# display_e7.net
KiCad netlist of a schematic drawn in EAGLE
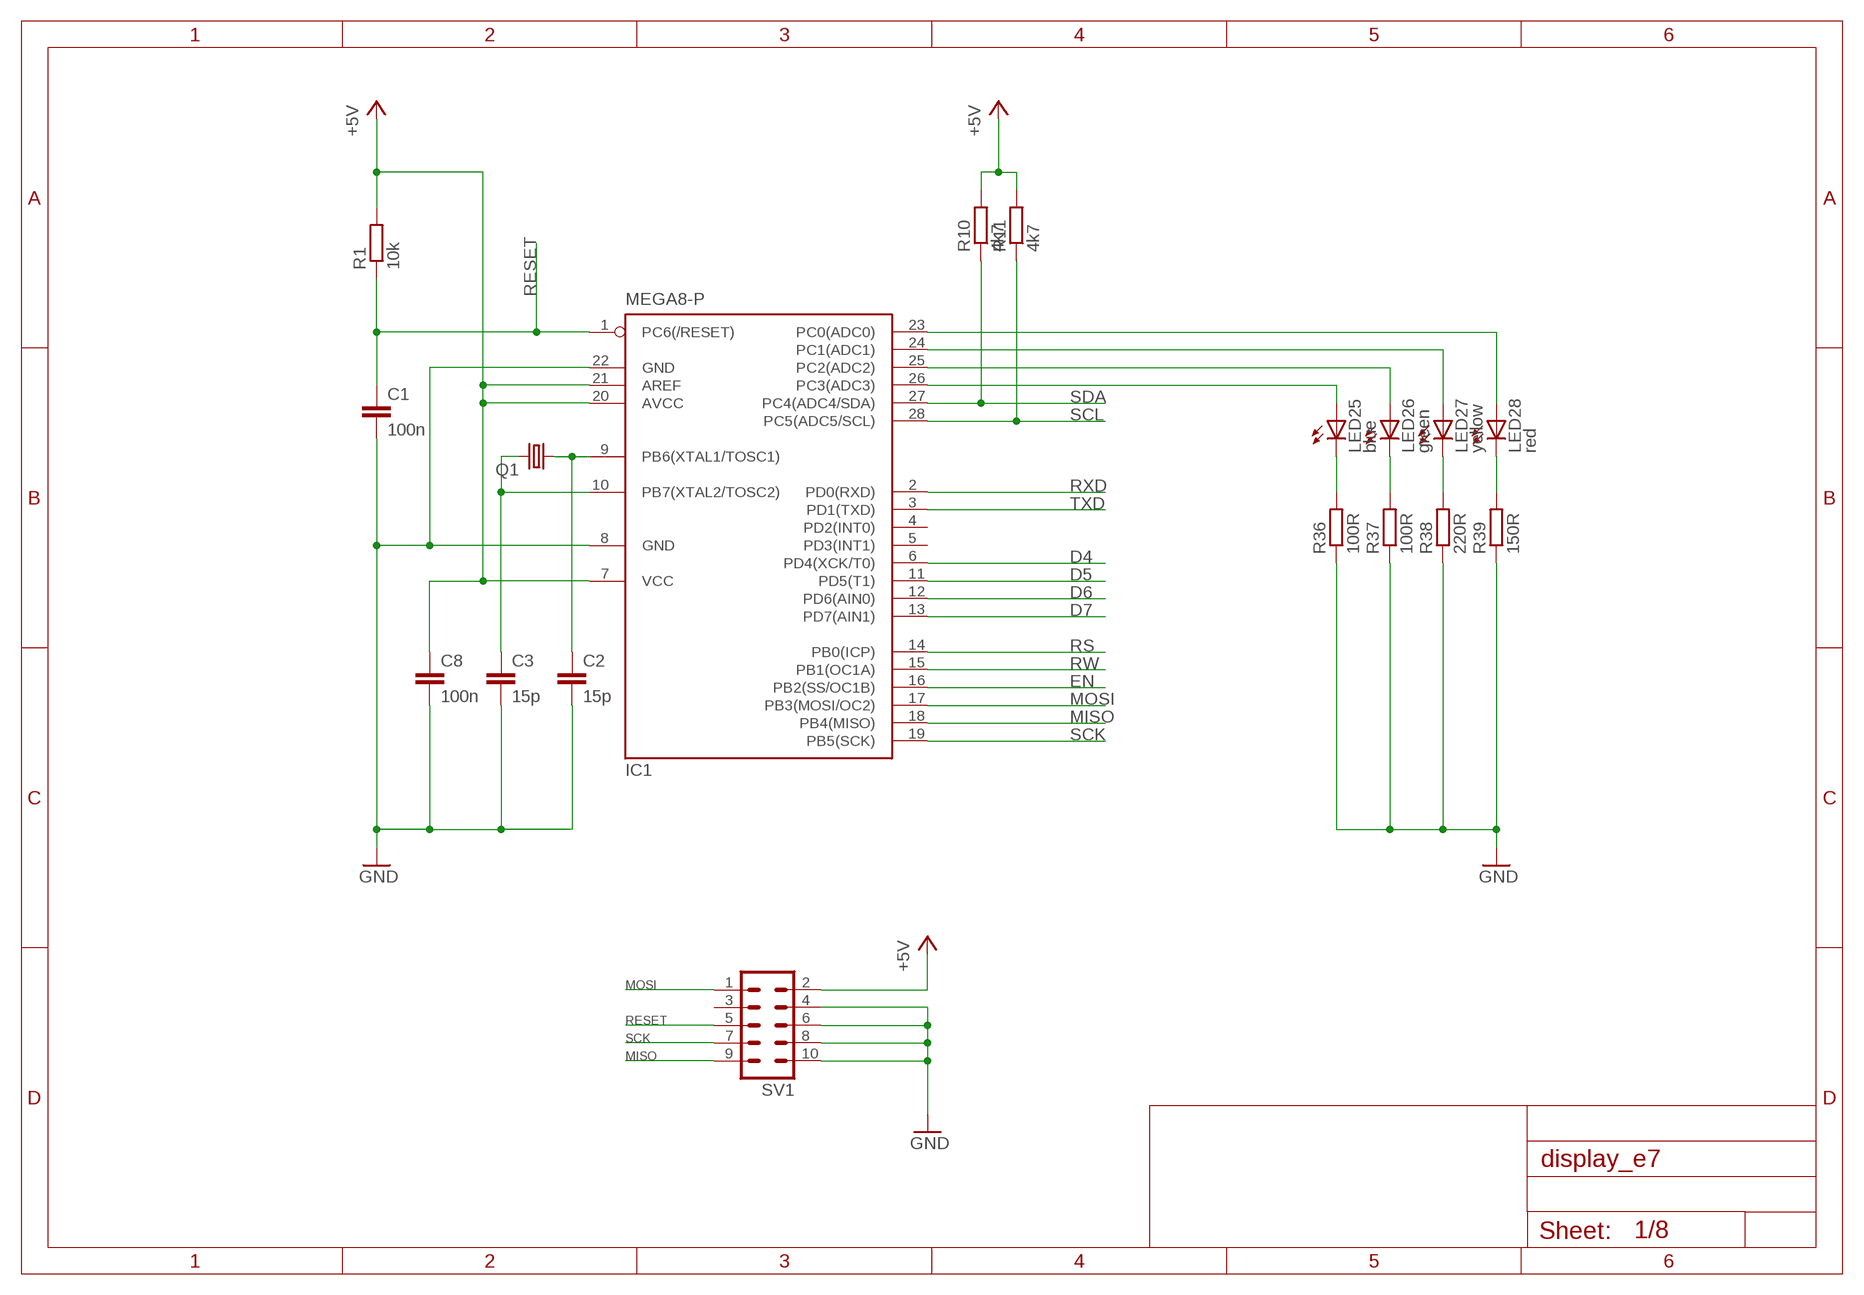
[diagram p0: schematic, sheet 1]
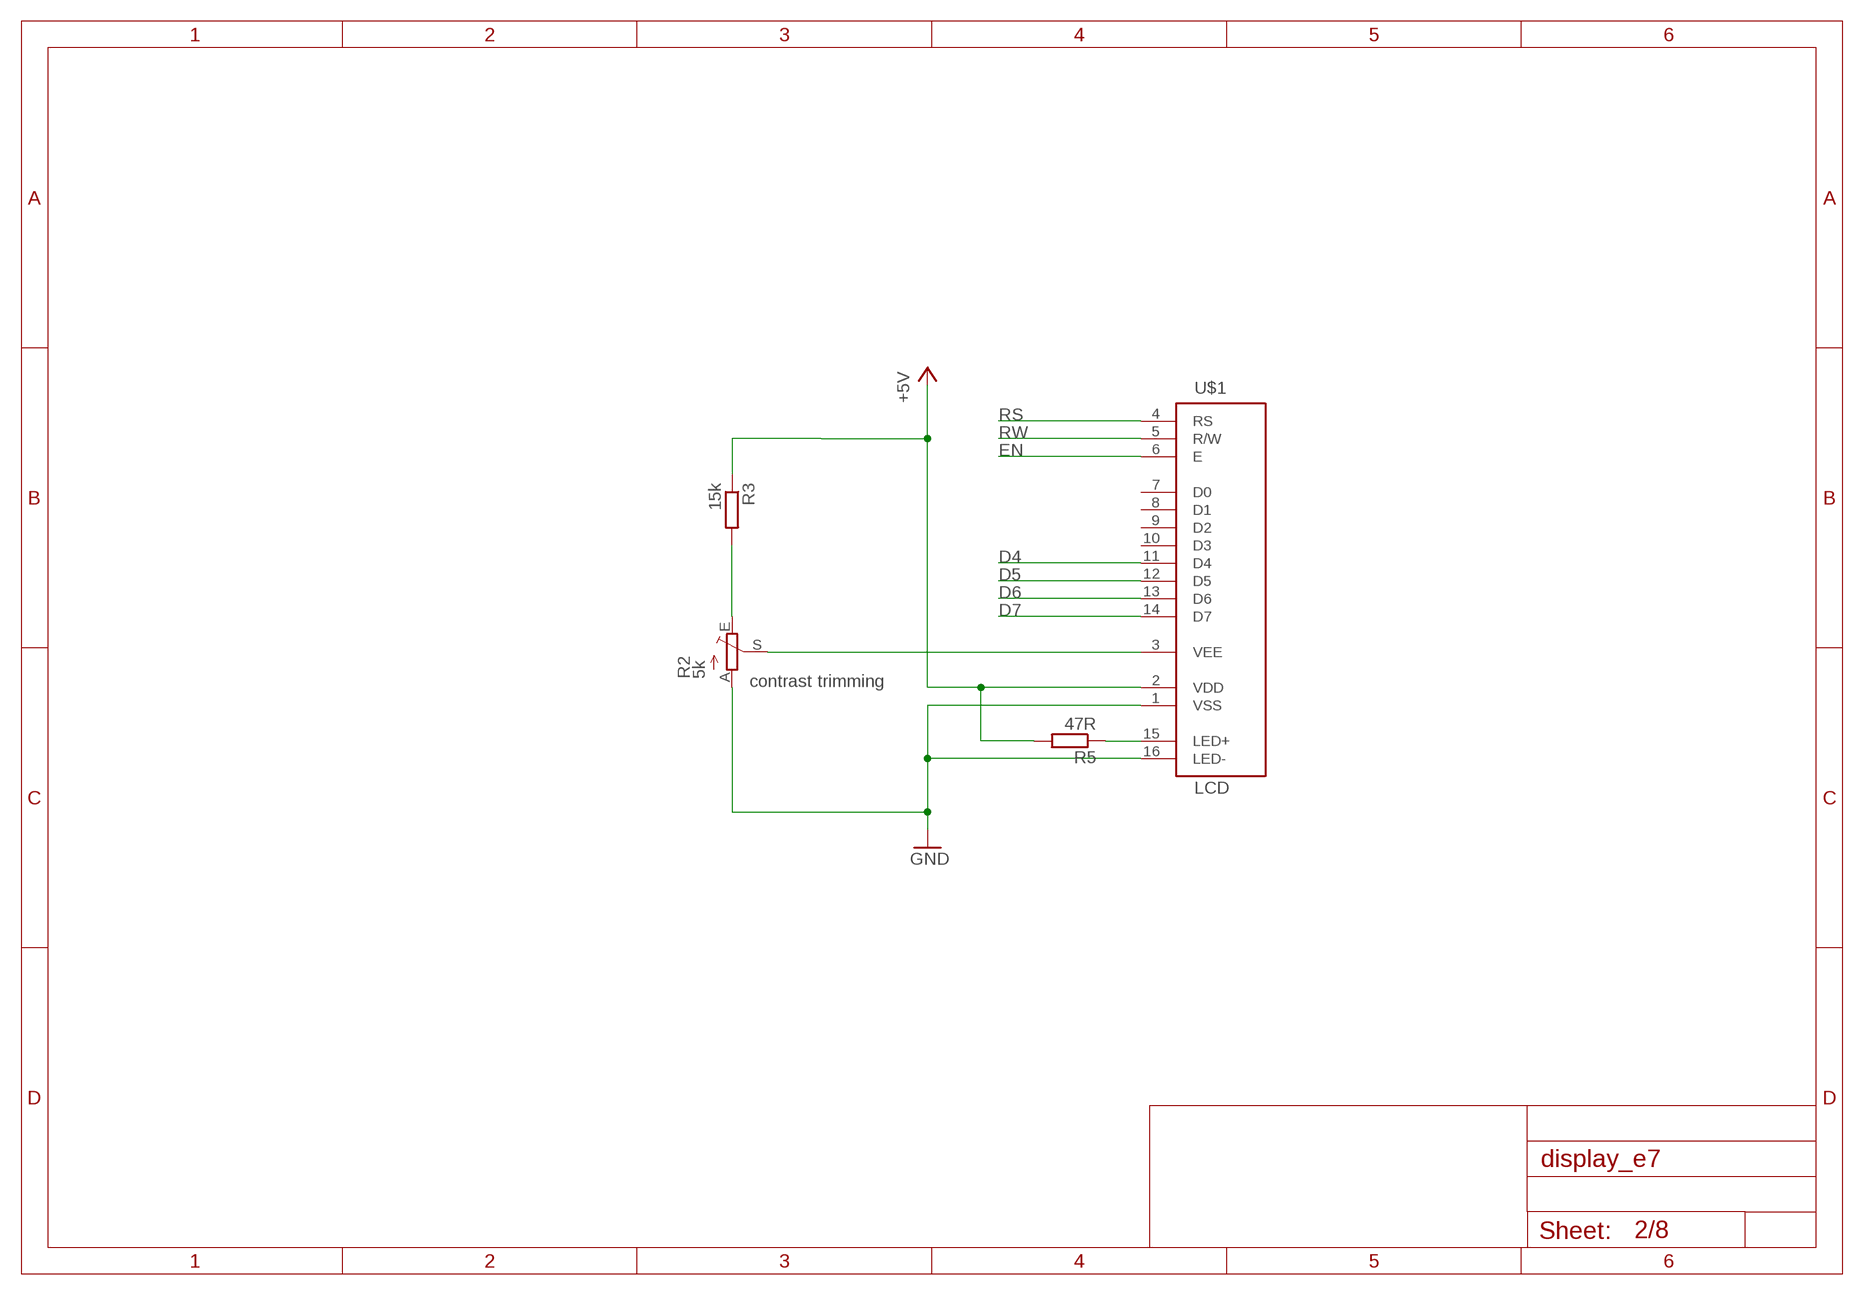
[diagram p1: schematic, sheet 2]
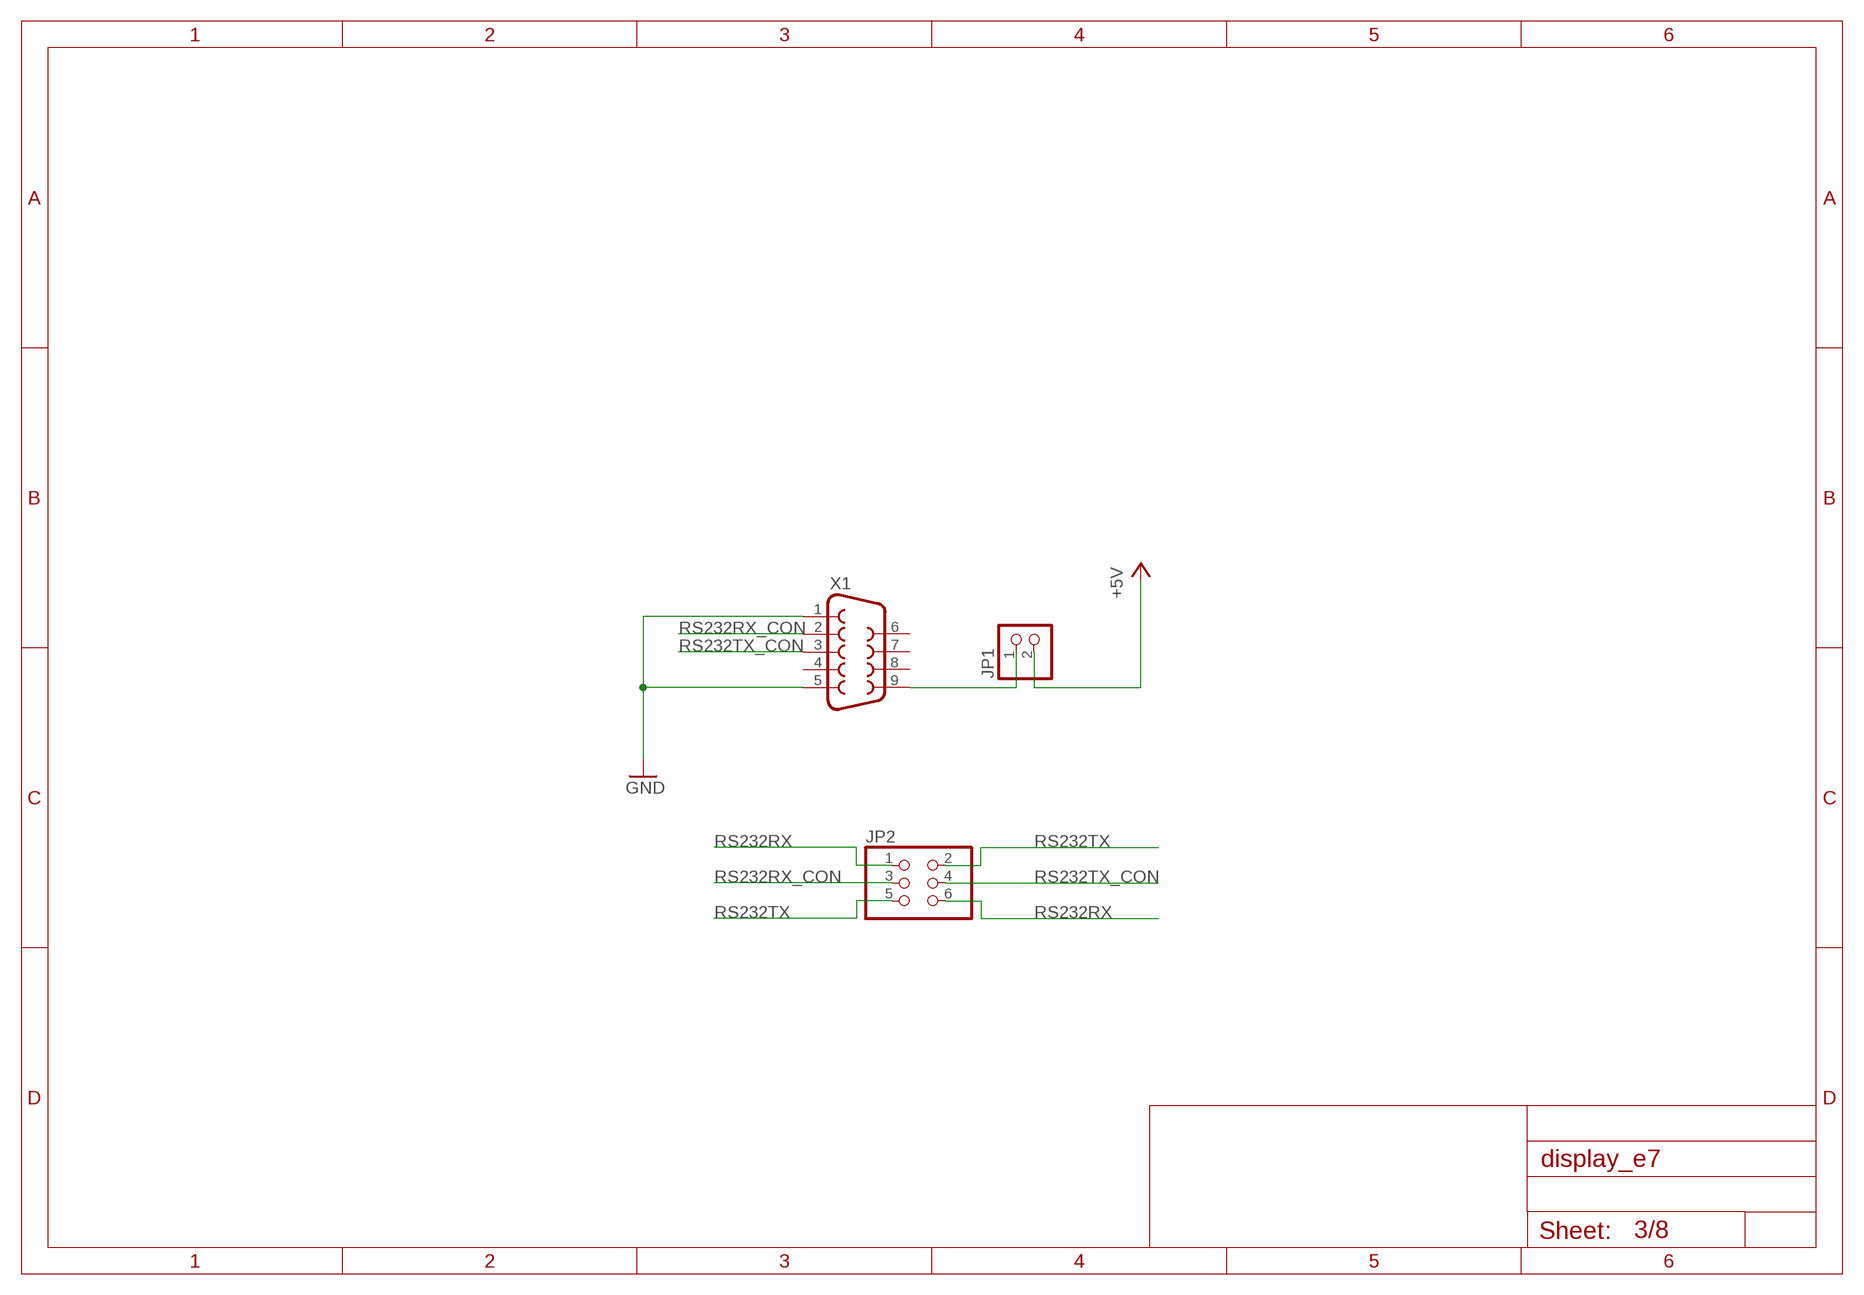
[diagram p2: schematic, sheet 3]
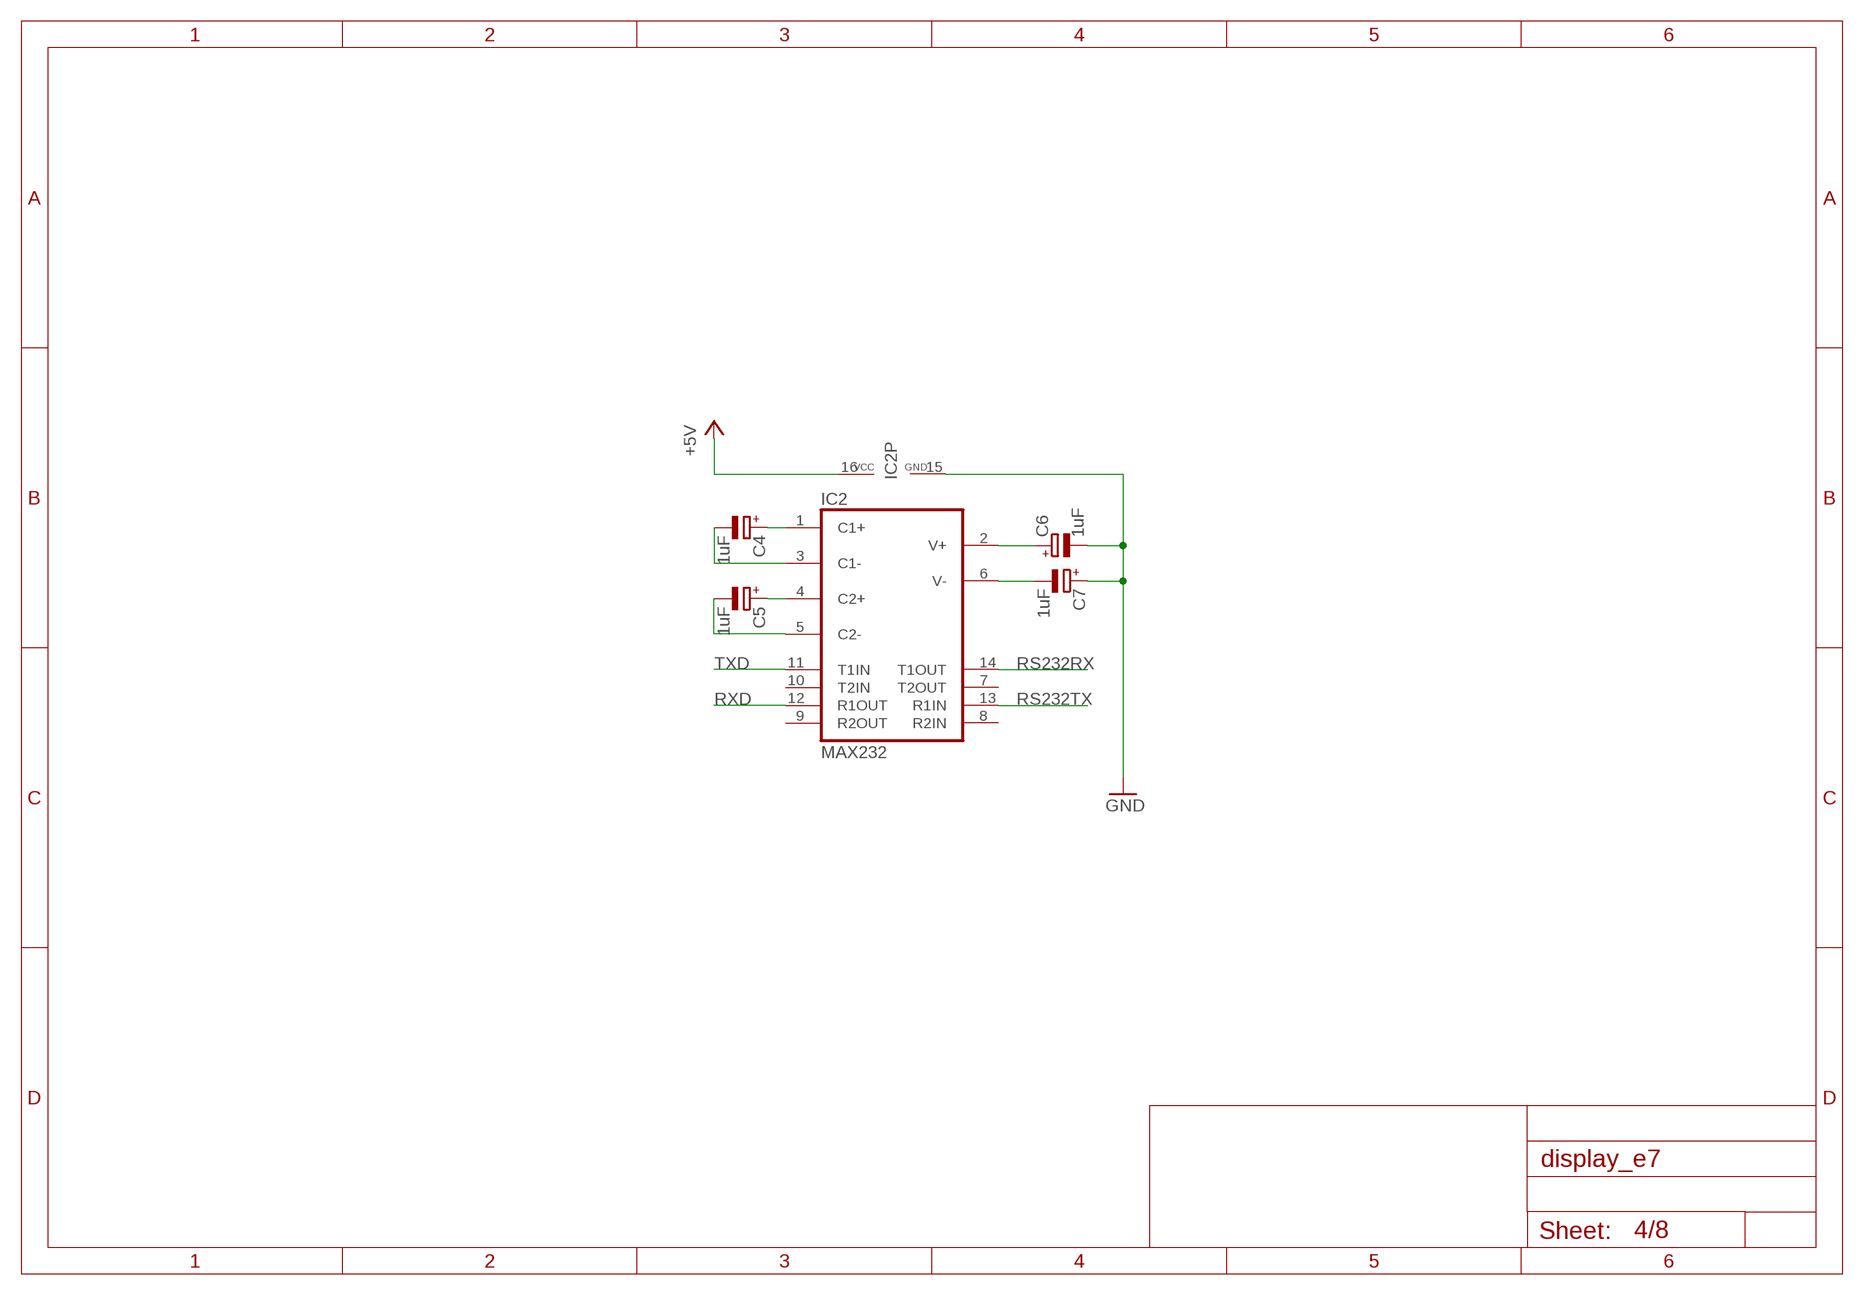
[diagram p3: schematic, sheet 4]
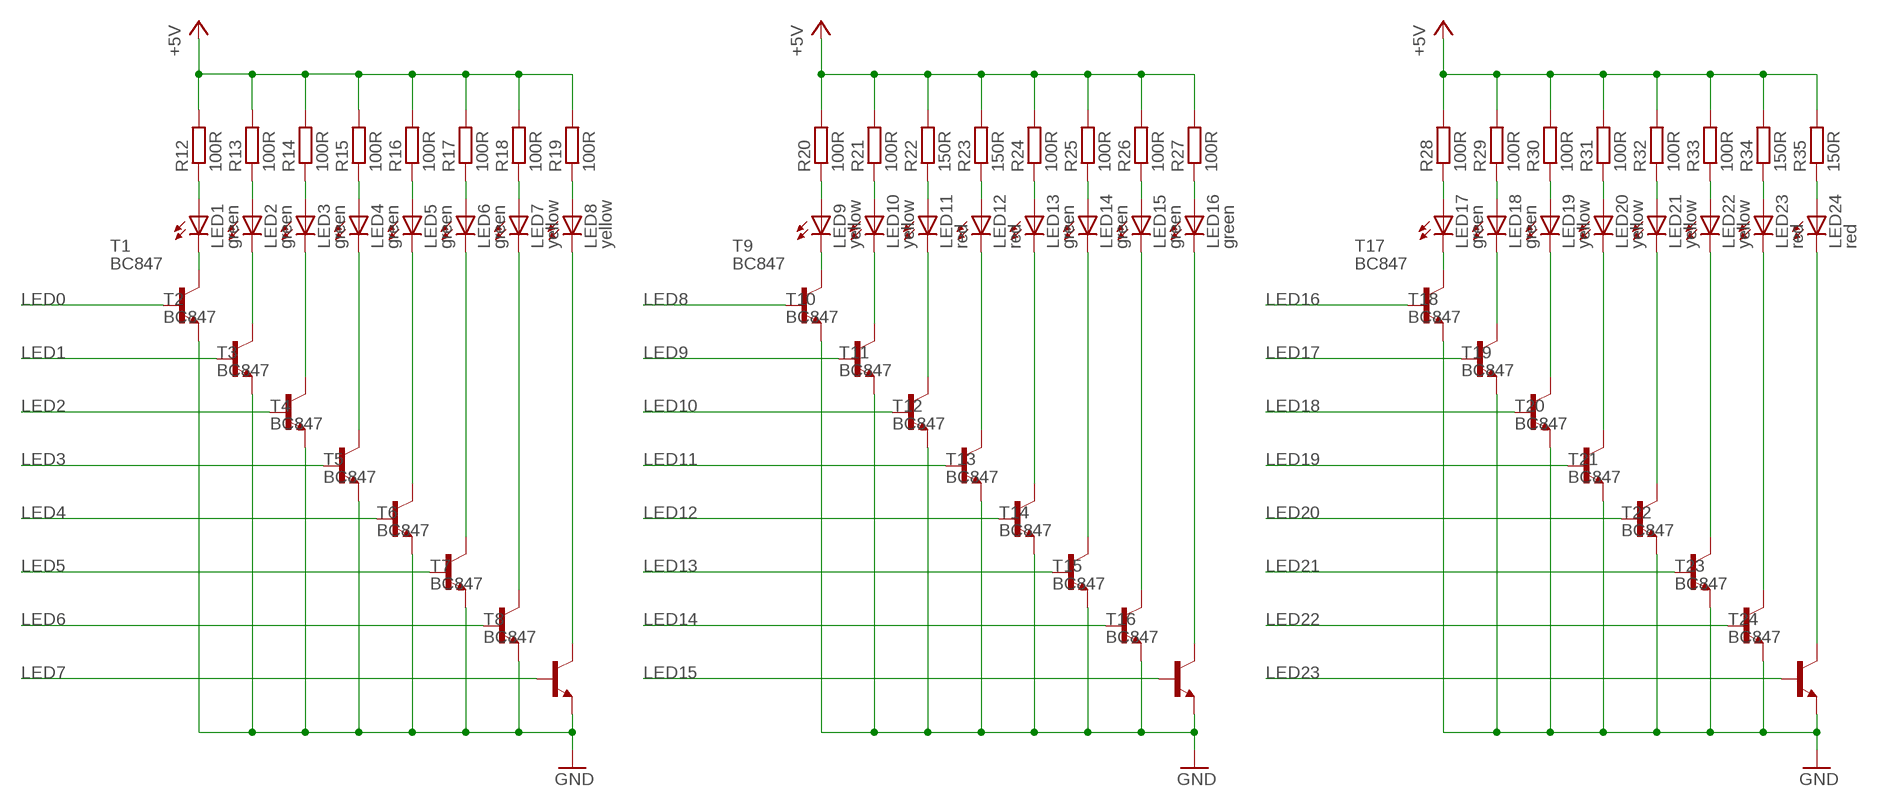
[diagram p4: schematic, sheet 5]
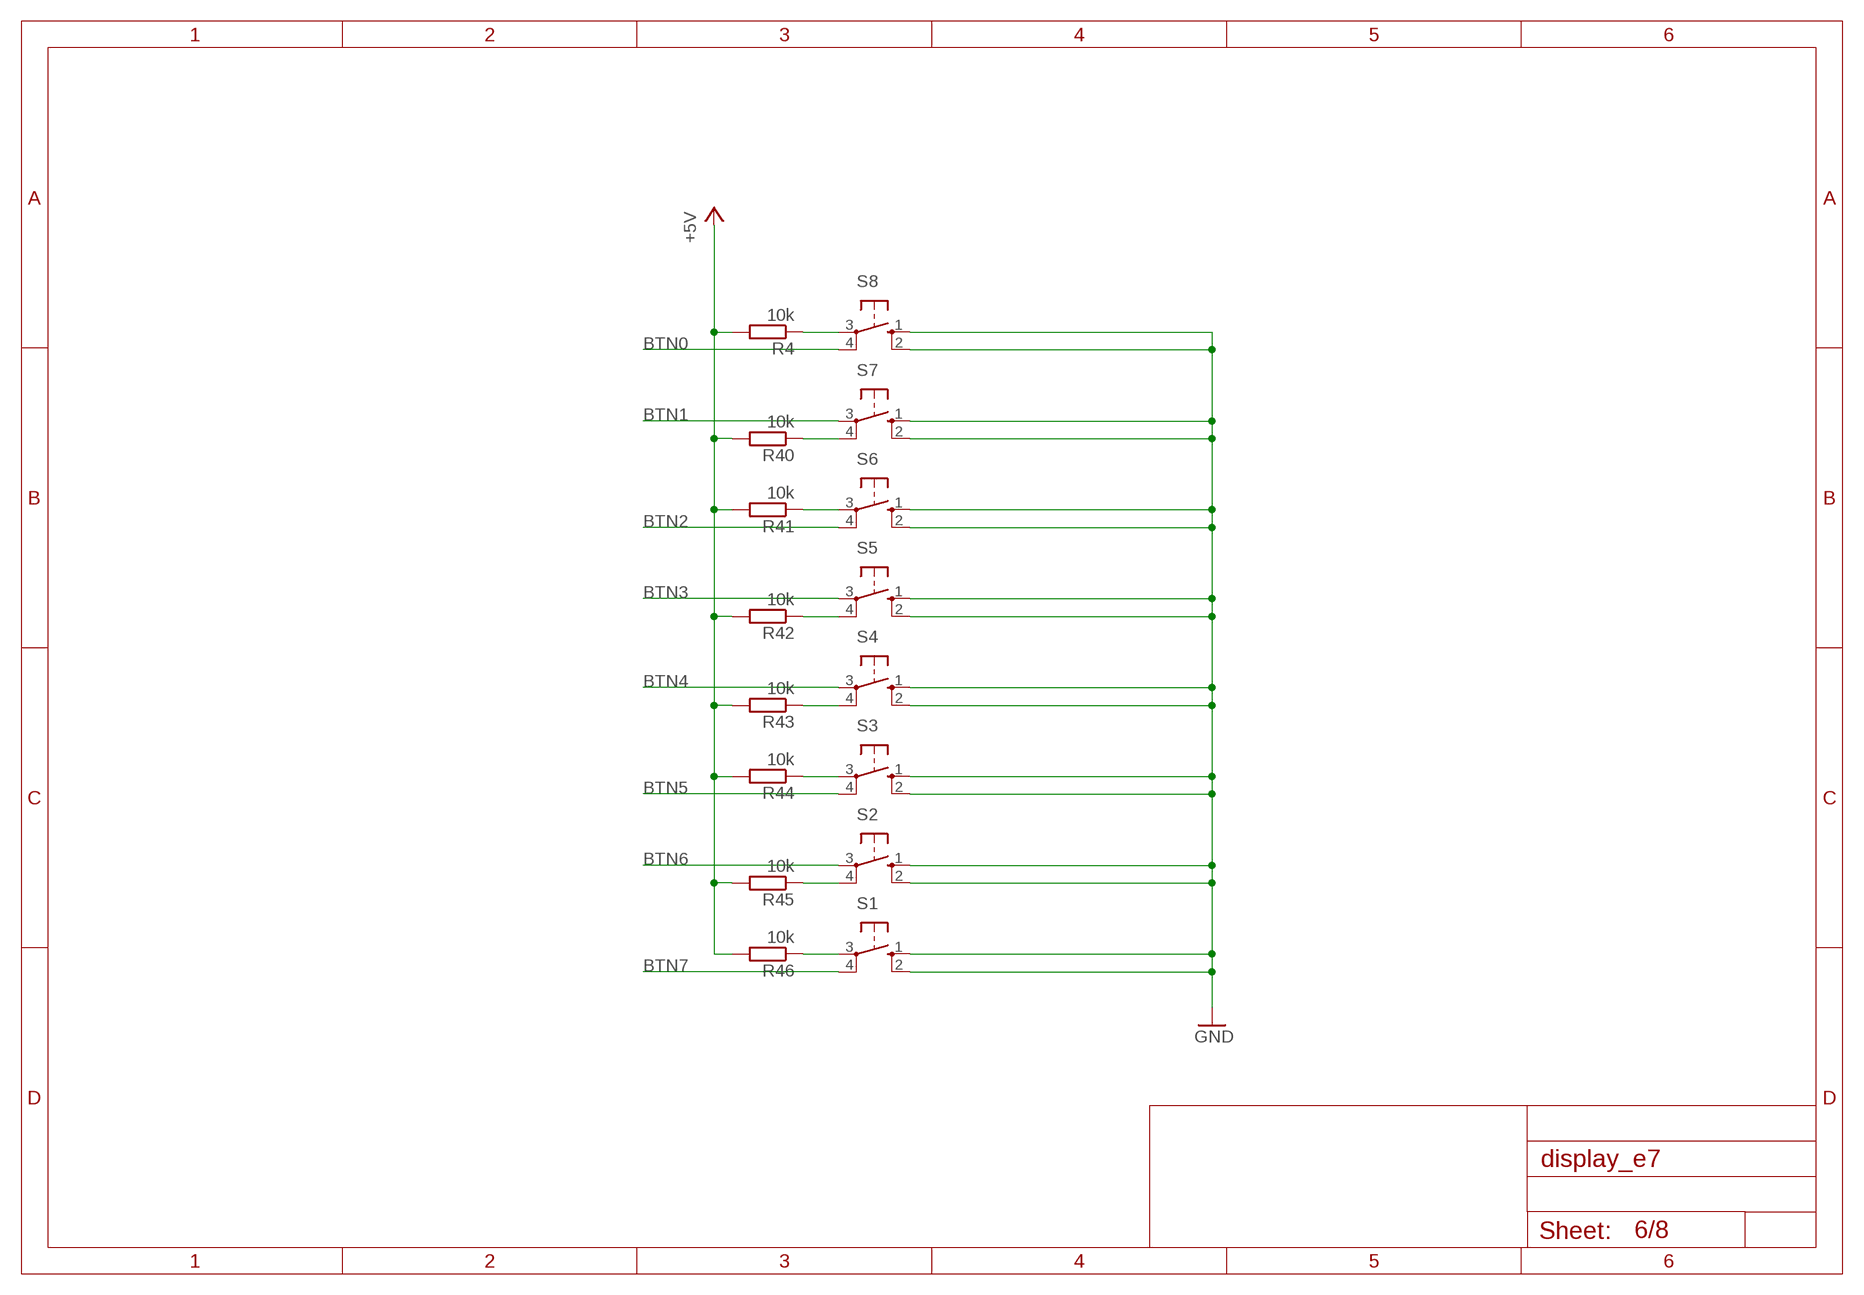
[diagram p5: schematic, sheet 6]
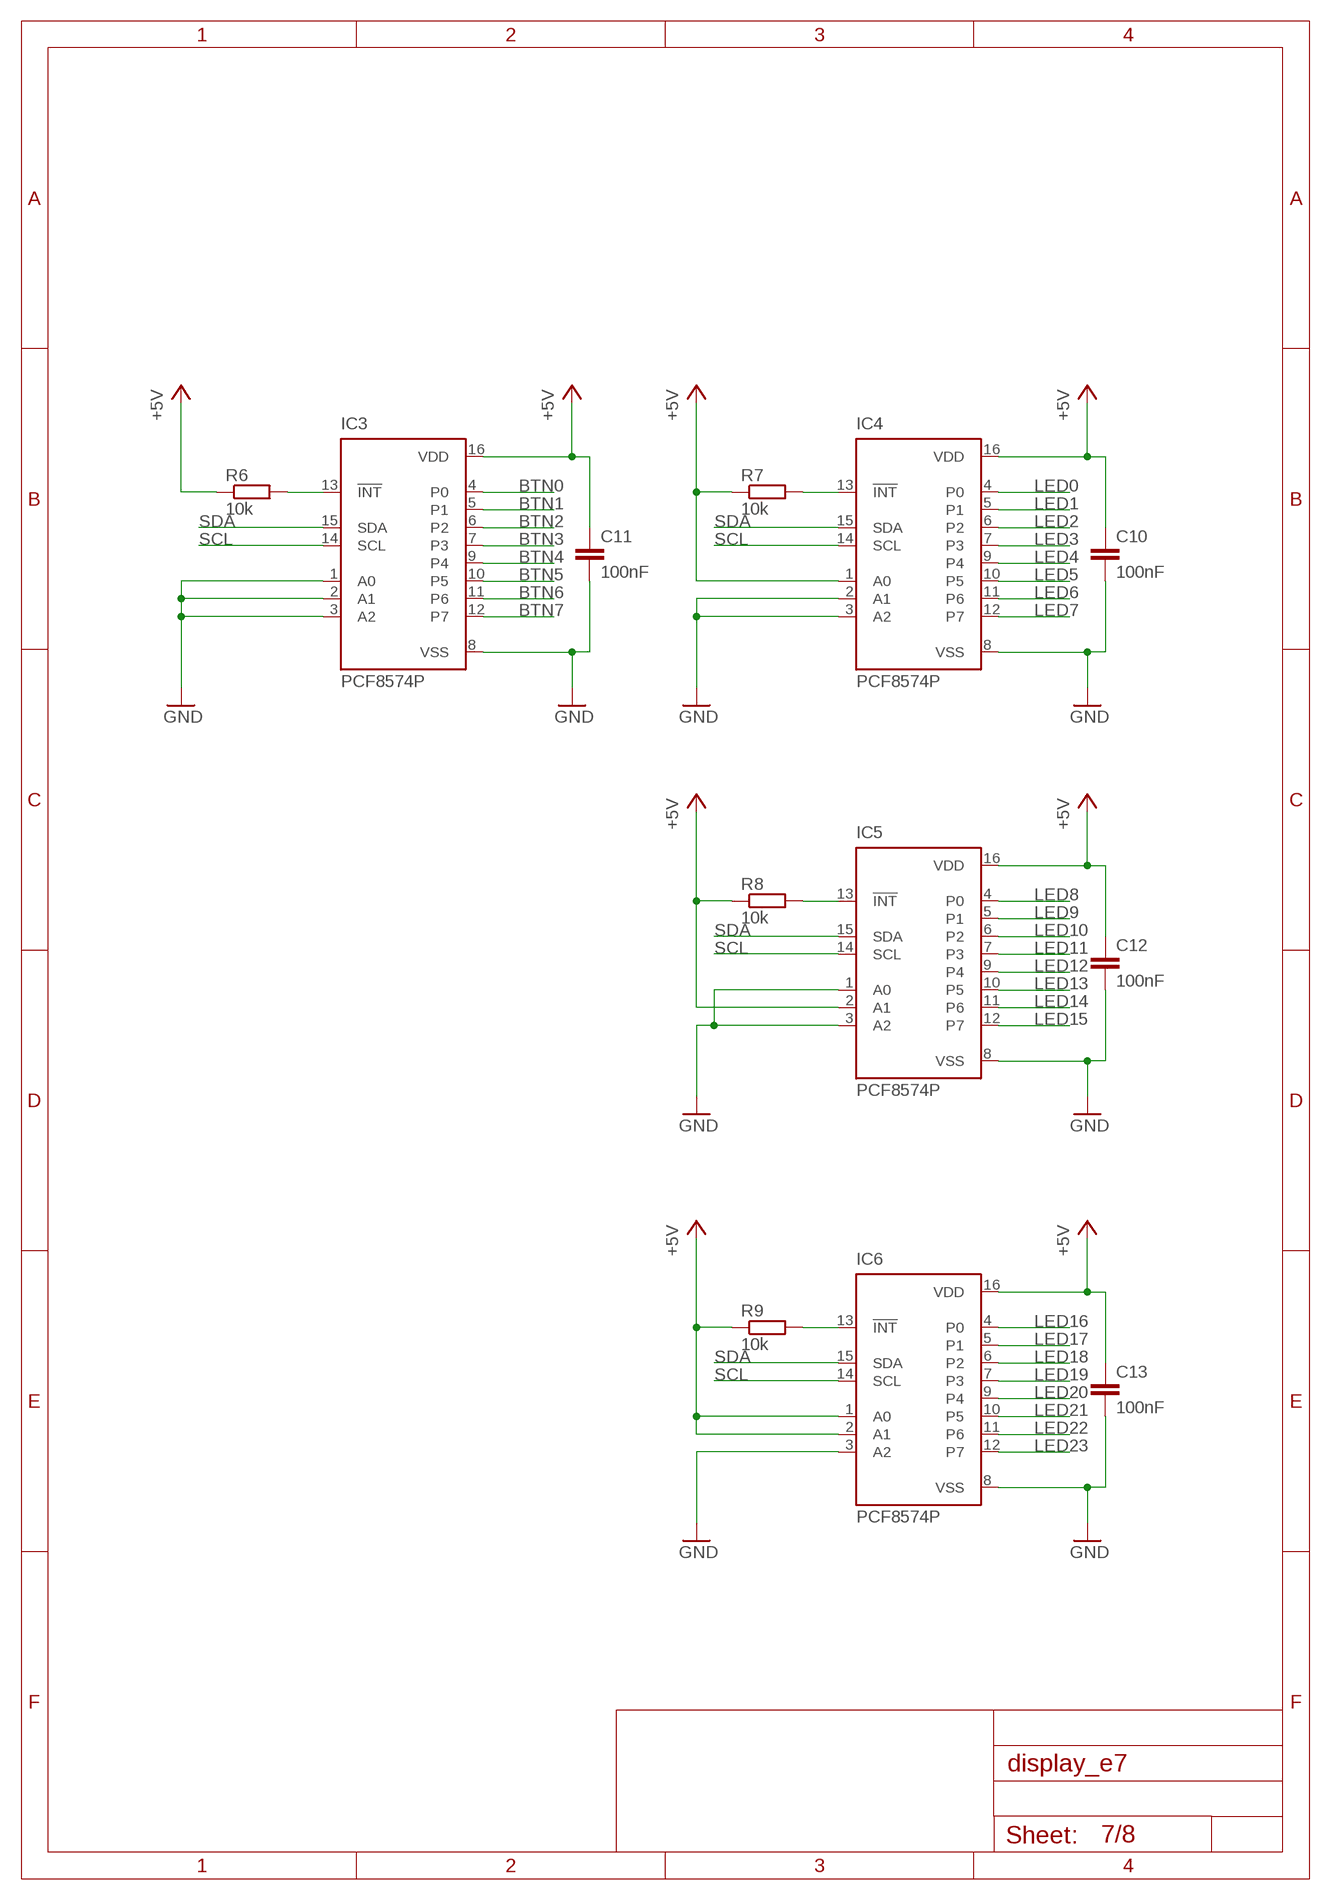
[diagram p6: schematic, sheet 7]
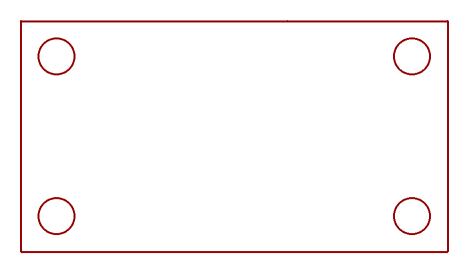
[diagram p7: schematic, sheet 8]

(export (version "E")
  (design (tool "Eeschema 10.0.6"))
  (components
    (comp (ref "C10")
      (value "100nF")
      (footprint "eagle-import:C025-025X050")
      (libsource (lib "eagle-import") (part "C-EU025-025X050"))
    )
    (comp (ref "C11")
      (value "100nF")
      (footprint "eagle-import:C025-025X050")
      (libsource (lib "eagle-import") (part "C-EU025-025X050"))
    )
    (comp (ref "C12")
      (value "100nF")
      (footprint "eagle-import:C025-025X050")
      (libsource (lib "eagle-import") (part "C-EU025-025X050"))
    )
    (comp (ref "C13")
      (value "100nF")
      (footprint "eagle-import:C025-025X050")
      (libsource (lib "eagle-import") (part "C-EU025-025X050"))
    )
    (comp (ref "IC3")
      (value "PCF8574P")
      (footprint "eagle-import:DIL16")
      (fields (field (name "MPN") "PCF8574PN"))
      (libsource (lib "eagle-import") (part "PCF8574P"))
    )
    (comp (ref "IC4")
      (value "PCF8574P")
      (footprint "eagle-import:DIL16")
      (fields (field (name "MPN") "PCF8574PN"))
      (libsource (lib "eagle-import") (part "PCF8574P"))
    )
    (comp (ref "IC5")
      (value "PCF8574P")
      (footprint "eagle-import:DIL16")
      (fields (field (name "MPN") "PCF8574PN"))
      (libsource (lib "eagle-import") (part "PCF8574P"))
    )
    (comp (ref "IC6")
      (value "PCF8574P")
      (footprint "eagle-import:DIL16")
      (fields (field (name "MPN") "PCF8574PN"))
      (libsource (lib "eagle-import") (part "PCF8574P"))
    )
    (comp (ref "R6")
      (value "10k")
      (footprint "eagle-import:0207_10")
      (libsource (lib "eagle-import") (part "R-EU_0207/10"))
    )
    (comp (ref "R7")
      (value "10k")
      (footprint "eagle-import:0207_10")
      (libsource (lib "eagle-import") (part "R-EU_0207/10"))
    )
    (comp (ref "R8")
      (value "10k")
      (footprint "eagle-import:0207_10")
      (libsource (lib "eagle-import") (part "R-EU_0207/10"))
    )
    (comp (ref "R9")
      (value "10k")
      (footprint "eagle-import:0207_10")
      (libsource (lib "eagle-import") (part "R-EU_0207/10"))
    )
    (comp (ref "JP1")
      (value "PINHD-1X2")
      (footprint "eagle-import:1X02")
      (libsource (lib "eagle-import") (part "PINHD-1X2"))
    )
    (comp (ref "JP2")
      (value "PINHD-2X3")
      (footprint "eagle-import:2X03")
      (libsource (lib "eagle-import") (part "PINHD-2X3"))
    )
    (comp (ref "X1")
      (value "F09HP")
      (footprint "eagle-import:F09HP")
      (libsource (lib "eagle-import") (part "F09HP"))
    )
    (comp (ref "U$2")
      (value "DISPLAY_FRAME")
      (footprint "eagle-import:DISPLAY_FRAME")
      (libsource (lib "eagle-import") (part "DISPLAY_FRAME"))
    )
    (comp (ref "R2")
      (value "5k")
      (footprint "eagle-import:PT-10")
      (libsource (lib "eagle-import") (part "TRIM_EU-PT10"))
    )
    (comp (ref "R3")
      (value "15k")
      (footprint "eagle-import:0207_10")
      (libsource (lib "eagle-import") (part "R-EU_0207/10"))
    )
    (comp (ref "R5")
      (value "47R")
      (footprint "eagle-import:0207_10")
      (libsource (lib "eagle-import") (part "R-EU_0207/10"))
    )
    (comp (ref "U$1")
      (value "LCD")
      (footprint "eagle-import:LCD")
      (libsource (lib "eagle-import") (part "LCD"))
    )
    (comp (ref "C1")
      (value "100n")
      (footprint "eagle-import:C025-025X050")
      (libsource (lib "eagle-import") (part "C-EU025-025X050"))
    )
    (comp (ref "C2")
      (value "15p")
      (footprint "eagle-import:C025-025X050")
      (libsource (lib "eagle-import") (part "C-EU025-025X050"))
    )
    (comp (ref "C3")
      (value "15p")
      (footprint "eagle-import:C025-025X050")
      (libsource (lib "eagle-import") (part "C-EU025-025X050"))
    )
    (comp (ref "C8")
      (value "100n")
      (footprint "eagle-import:C025-025X050")
      (libsource (lib "eagle-import") (part "C-EU025-025X050"))
    )
    (comp (ref "IC1")
      (value "MEGA8-P")
      (footprint "eagle-import:DIL28-3")
      (libsource (lib "eagle-import") (part "MEGA8-P"))
    )
    (comp (ref "LED25")
      (value "blue")
      (footprint "eagle-import:LED3MM")
      (libsource (lib "eagle-import") (part "LED3MM"))
    )
    (comp (ref "LED26")
      (value "green")
      (footprint "eagle-import:LED3MM")
      (libsource (lib "eagle-import") (part "LED3MM"))
    )
    (comp (ref "LED27")
      (value "yellow")
      (footprint "eagle-import:LED3MM")
      (libsource (lib "eagle-import") (part "LED3MM"))
    )
    (comp (ref "LED28")
      (value "red")
      (footprint "eagle-import:LED3MM")
      (libsource (lib "eagle-import") (part "LED3MM"))
    )
    (comp (ref "Q1")
      (value "CRYSTALHC49U-V")
      (footprint "eagle-import:HC49U-V")
      (libsource (lib "eagle-import") (part "CRYSTALHC49U-V"))
    )
    (comp (ref "R1")
      (value "10k")
      (footprint "eagle-import:0207_10")
      (libsource (lib "eagle-import") (part "R-EU_0207/10"))
    )
    (comp (ref "R10")
      (value "4k7")
      (footprint "eagle-import:0207_10")
      (libsource (lib "eagle-import") (part "R-EU_0207/10"))
    )
    (comp (ref "R11")
      (value "4k7")
      (footprint "eagle-import:0207_10")
      (libsource (lib "eagle-import") (part "R-EU_0207/10"))
    )
    (comp (ref "R36")
      (value "100R")
      (footprint "eagle-import:0207_10")
      (libsource (lib "eagle-import") (part "R-EU_0207/10"))
    )
    (comp (ref "R37")
      (value "100R")
      (footprint "eagle-import:0207_10")
      (libsource (lib "eagle-import") (part "R-EU_0207/10"))
    )
    (comp (ref "R38")
      (value "220R")
      (footprint "eagle-import:0207_10")
      (libsource (lib "eagle-import") (part "R-EU_0207/10"))
    )
    (comp (ref "R39")
      (value "150R")
      (footprint "eagle-import:0207_10")
      (libsource (lib "eagle-import") (part "R-EU_0207/10"))
    )
    (comp (ref "SV1")
      (value "ML10")
      (footprint "eagle-import:ML10")
      (libsource (lib "eagle-import") (part "ML10"))
    )
    (comp (ref "LED1")
      (value "green")
      (footprint "eagle-import:LED5MM")
      (libsource (lib "eagle-import") (part "LED5MM"))
    )
    (comp (ref "LED2")
      (value "green")
      (footprint "eagle-import:LED5MM")
      (libsource (lib "eagle-import") (part "LED5MM"))
    )
    (comp (ref "LED3")
      (value "green")
      (footprint "eagle-import:LED5MM")
      (libsource (lib "eagle-import") (part "LED5MM"))
    )
    (comp (ref "LED4")
      (value "green")
      (footprint "eagle-import:LED5MM")
      (libsource (lib "eagle-import") (part "LED5MM"))
    )
    (comp (ref "LED5")
      (value "green")
      (footprint "eagle-import:LED5MM")
      (libsource (lib "eagle-import") (part "LED5MM"))
    )
    (comp (ref "LED6")
      (value "green")
      (footprint "eagle-import:LED5MM")
      (libsource (lib "eagle-import") (part "LED5MM"))
    )
    (comp (ref "LED7")
      (value "yellow")
      (footprint "eagle-import:LED5MM")
      (libsource (lib "eagle-import") (part "LED5MM"))
    )
    (comp (ref "LED8")
      (value "yellow")
      (footprint "eagle-import:LED5MM")
      (libsource (lib "eagle-import") (part "LED5MM"))
    )
    (comp (ref "LED9")
      (value "yellow")
      (footprint "eagle-import:LED5MM")
      (libsource (lib "eagle-import") (part "LED5MM"))
    )
    (comp (ref "LED10")
      (value "yellow")
      (footprint "eagle-import:LED5MM")
      (libsource (lib "eagle-import") (part "LED5MM"))
    )
    (comp (ref "LED11")
      (value "red")
      (footprint "eagle-import:LED5MM")
      (libsource (lib "eagle-import") (part "LED5MM"))
    )
    (comp (ref "LED12")
      (value "red")
      (footprint "eagle-import:LED5MM")
      (libsource (lib "eagle-import") (part "LED5MM"))
    )
    (comp (ref "LED13")
      (value "green")
      (footprint "eagle-import:LED5MM")
      (libsource (lib "eagle-import") (part "LED5MM"))
    )
    (comp (ref "LED14")
      (value "green")
      (footprint "eagle-import:LED5MM")
      (libsource (lib "eagle-import") (part "LED5MM"))
    )
    (comp (ref "LED15")
      (value "green")
      (footprint "eagle-import:LED5MM")
      (libsource (lib "eagle-import") (part "LED5MM"))
    )
    (comp (ref "LED16")
      (value "green")
      (footprint "eagle-import:LED5MM")
      (libsource (lib "eagle-import") (part "LED5MM"))
    )
    (comp (ref "LED17")
      (value "green")
      (footprint "eagle-import:LED5MM")
      (fields (field (name "SPICEPREFIX") "L"))
      (libsource (lib "eagle-import") (part "LED5MM"))
    )
    (comp (ref "LED18")
      (value "green")
      (footprint "eagle-import:LED5MM")
      (fields (field (name "SPICEPREFIX") "X"))
      (libsource (lib "eagle-import") (part "LED5MM"))
    )
    (comp (ref "LED19")
      (value "yellow")
      (footprint "eagle-import:LED5MM")
      (fields (field (name "SPICEPREFIX") "B"))
      (libsource (lib "eagle-import") (part "LED5MM"))
    )
    (comp (ref "LED20")
      (value "yellow")
      (footprint "eagle-import:LED5MM")
      (fields (field (name "SPICEPREFIX") "L"))
      (libsource (lib "eagle-import") (part "LED5MM"))
    )
    (comp (ref "LED21")
      (value "yellow")
      (footprint "eagle-import:LED5MM")
      (fields (field (name "SPICEPREFIX") "L"))
      (libsource (lib "eagle-import") (part "LED5MM"))
    )
    (comp (ref "LED22")
      (value "yellow")
      (footprint "eagle-import:LED5MM")
      (fields (field (name "SPICEPREFIX") "L"))
      (libsource (lib "eagle-import") (part "LED5MM"))
    )
    (comp (ref "LED23")
      (value "red")
      (footprint "eagle-import:LED5MM")
      (fields (field (name "SPICEPREFIX") "L"))
      (libsource (lib "eagle-import") (part "LED5MM"))
    )
    (comp (ref "LED24")
      (value "red")
      (footprint "eagle-import:LED5MM")
      (fields (field (name "SPICEPREFIX") "L"))
      (libsource (lib "eagle-import") (part "LED5MM"))
    )
    (comp (ref "R12")
      (value "100R")
      (footprint "eagle-import:0207_10")
      (libsource (lib "eagle-import") (part "R-EU_0207/10"))
    )
    (comp (ref "R13")
      (value "100R")
      (footprint "eagle-import:0207_10")
      (libsource (lib "eagle-import") (part "R-EU_0207/10"))
    )
    (comp (ref "R14")
      (value "100R")
      (footprint "eagle-import:0207_10")
      (libsource (lib "eagle-import") (part "R-EU_0207/10"))
    )
    (comp (ref "R15")
      (value "100R")
      (footprint "eagle-import:0207_10")
      (libsource (lib "eagle-import") (part "R-EU_0207/10"))
    )
    (comp (ref "R16")
      (value "100R")
      (footprint "eagle-import:0207_10")
      (libsource (lib "eagle-import") (part "R-EU_0207/10"))
    )
    (comp (ref "R17")
      (value "100R")
      (footprint "eagle-import:0207_10")
      (libsource (lib "eagle-import") (part "R-EU_0207/10"))
    )
    (comp (ref "R18")
      (value "100R")
      (footprint "eagle-import:0207_10")
      (libsource (lib "eagle-import") (part "R-EU_0207/10"))
    )
    (comp (ref "R19")
      (value "100R")
      (footprint "eagle-import:0207_10")
      (libsource (lib "eagle-import") (part "R-EU_0207/10"))
    )
    (comp (ref "R20")
      (value "100R")
      (footprint "eagle-import:0207_10")
      (libsource (lib "eagle-import") (part "R-EU_0207/10"))
    )
    (comp (ref "R21")
      (value "100R")
      (footprint "eagle-import:0207_10")
      (libsource (lib "eagle-import") (part "R-EU_0207/10"))
    )
    (comp (ref "R22")
      (value "150R")
      (footprint "eagle-import:0207_10")
      (libsource (lib "eagle-import") (part "R-EU_0207/10"))
    )
    (comp (ref "R23")
      (value "150R")
      (footprint "eagle-import:0207_10")
      (libsource (lib "eagle-import") (part "R-EU_0207/10"))
    )
    (comp (ref "R24")
      (value "100R")
      (footprint "eagle-import:0207_10")
      (libsource (lib "eagle-import") (part "R-EU_0207/10"))
    )
    (comp (ref "R25")
      (value "100R")
      (footprint "eagle-import:0207_10")
      (libsource (lib "eagle-import") (part "R-EU_0207/10"))
    )
    (comp (ref "R26")
      (value "100R")
      (footprint "eagle-import:0207_10")
      (libsource (lib "eagle-import") (part "R-EU_0207/10"))
    )
    (comp (ref "R27")
      (value "100R")
      (footprint "eagle-import:0207_10")
      (libsource (lib "eagle-import") (part "R-EU_0207/10"))
    )
    (comp (ref "R28")
      (value "100R")
      (footprint "eagle-import:0207_10")
      (libsource (lib "eagle-import") (part "R-EU_0207/10"))
    )
    (comp (ref "R29")
      (value "100R")
      (footprint "eagle-import:0207_10")
      (libsource (lib "eagle-import") (part "R-EU_0207/10"))
    )
    (comp (ref "R30")
      (value "100R")
      (footprint "eagle-import:0207_10")
      (libsource (lib "eagle-import") (part "R-EU_0207/10"))
    )
    (comp (ref "R31")
      (value "100R")
      (footprint "eagle-import:0207_10")
      (libsource (lib "eagle-import") (part "R-EU_0207/10"))
    )
    (comp (ref "R32")
      (value "100R")
      (footprint "eagle-import:0207_10")
      (libsource (lib "eagle-import") (part "R-EU_0207/10"))
    )
    (comp (ref "R33")
      (value "100R")
      (footprint "eagle-import:0207_10")
      (libsource (lib "eagle-import") (part "R-EU_0207/10"))
    )
    (comp (ref "R34")
      (value "150R")
      (footprint "eagle-import:0207_10")
      (libsource (lib "eagle-import") (part "R-EU_0207/10"))
    )
    (comp (ref "R35")
      (value "150R")
      (footprint "eagle-import:0207_10")
      (libsource (lib "eagle-import") (part "R-EU_0207/10"))
    )
    (comp (ref "T1")
      (value "BC847")
      (footprint "eagle-import:SOT23")
      (libsource (lib "eagle-import") (part "BC847"))
    )
    (comp (ref "T2")
      (value "BC847")
      (footprint "eagle-import:SOT23")
      (libsource (lib "eagle-import") (part "BC847"))
    )
    (comp (ref "T3")
      (value "BC847")
      (footprint "eagle-import:SOT23")
      (libsource (lib "eagle-import") (part "BC847"))
    )
    (comp (ref "T4")
      (value "BC847")
      (footprint "eagle-import:SOT23")
      (libsource (lib "eagle-import") (part "BC847"))
    )
    (comp (ref "T5")
      (value "BC847")
      (footprint "eagle-import:SOT23")
      (libsource (lib "eagle-import") (part "BC847"))
    )
    (comp (ref "T6")
      (value "BC847")
      (footprint "eagle-import:SOT23")
      (libsource (lib "eagle-import") (part "BC847"))
    )
    (comp (ref "T7")
      (value "BC847")
      (footprint "eagle-import:SOT23")
      (libsource (lib "eagle-import") (part "BC847"))
    )
    (comp (ref "T8")
      (value "BC847")
      (footprint "eagle-import:SOT23")
      (libsource (lib "eagle-import") (part "BC847"))
    )
    (comp (ref "T9")
      (value "BC847")
      (footprint "eagle-import:SOT23")
      (libsource (lib "eagle-import") (part "BC847"))
    )
    (comp (ref "T10")
      (value "BC847")
      (footprint "eagle-import:SOT23")
      (libsource (lib "eagle-import") (part "BC847"))
    )
    (comp (ref "T11")
      (value "BC847")
      (footprint "eagle-import:SOT23")
      (libsource (lib "eagle-import") (part "BC847"))
    )
    (comp (ref "T12")
      (value "BC847")
      (footprint "eagle-import:SOT23")
      (libsource (lib "eagle-import") (part "BC847"))
    )
    (comp (ref "T13")
      (value "BC847")
      (footprint "eagle-import:SOT23")
      (libsource (lib "eagle-import") (part "BC847"))
    )
    (comp (ref "T14")
      (value "BC847")
      (footprint "eagle-import:SOT23")
      (libsource (lib "eagle-import") (part "BC847"))
    )
    (comp (ref "T15")
      (value "BC847")
      (footprint "eagle-import:SOT23")
      (libsource (lib "eagle-import") (part "BC847"))
    )
    (comp (ref "T16")
      (value "BC847")
      (footprint "eagle-import:SOT23")
      (fields (field (name "SPICEPREFIX") "J"))
      (libsource (lib "eagle-import") (part "BC847"))
    )
    (comp (ref "T17")
      (value "BC847")
      (footprint "eagle-import:SOT23")
      (libsource (lib "eagle-import") (part "BC847"))
    )
    (comp (ref "T18")
      (value "BC847")
      (footprint "eagle-import:SOT23")
      (libsource (lib "eagle-import") (part "BC847"))
    )
    (comp (ref "T19")
      (value "BC847")
      (footprint "eagle-import:SOT23")
      (libsource (lib "eagle-import") (part "BC847"))
    )
    (comp (ref "T20")
      (value "BC847")
      (footprint "eagle-import:SOT23")
      (libsource (lib "eagle-import") (part "BC847"))
    )
    (comp (ref "T21")
      (value "BC847")
      (footprint "eagle-import:SOT23")
      (libsource (lib "eagle-import") (part "BC847"))
    )
    (comp (ref "T22")
      (value "BC847")
      (footprint "eagle-import:SOT23")
      (libsource (lib "eagle-import") (part "BC847"))
    )
    (comp (ref "T23")
      (value "BC847")
      (footprint "eagle-import:SOT23")
      (libsource (lib "eagle-import") (part "BC847"))
    )
    (comp (ref "T24")
      (value "BC847")
      (footprint "eagle-import:SOT23")
      (libsource (lib "eagle-import") (part "BC847"))
    )
    (comp (ref "R4")
      (value "10k")
      (footprint "eagle-import:R0805")
      (libsource (lib "eagle-import") (part "R-EU_R0805"))
    )
    (comp (ref "R40")
      (value "10k")
      (footprint "eagle-import:R0805")
      (libsource (lib "eagle-import") (part "R-EU_R0805"))
    )
    (comp (ref "R41")
      (value "10k")
      (footprint "eagle-import:R0805")
      (libsource (lib "eagle-import") (part "R-EU_R0805"))
    )
    (comp (ref "R42")
      (value "10k")
      (footprint "eagle-import:R0805")
      (libsource (lib "eagle-import") (part "R-EU_R0805"))
    )
    (comp (ref "R43")
      (value "10k")
      (footprint "eagle-import:R0805")
      (libsource (lib "eagle-import") (part "R-EU_R0805"))
    )
    (comp (ref "R44")
      (value "10k")
      (footprint "eagle-import:R0805")
      (libsource (lib "eagle-import") (part "R-EU_R0805"))
    )
    (comp (ref "R45")
      (value "10k")
      (footprint "eagle-import:R0805")
      (libsource (lib "eagle-import") (part "R-EU_R0805"))
    )
    (comp (ref "R46")
      (value "10k")
      (footprint "eagle-import:R0805")
      (libsource (lib "eagle-import") (part "R-EU_R0805"))
    )
    (comp (ref "S1")
      (value "10-XX")
      (footprint "eagle-import:B3F-10XX")
      (fields (field (name "MPN") "B3F-1000"))
      (libsource (lib "eagle-import") (part "10-XX"))
    )
    (comp (ref "S2")
      (value "10-XX")
      (footprint "eagle-import:B3F-10XX")
      (fields (field (name "MPN") "B3F-1000"))
      (libsource (lib "eagle-import") (part "10-XX"))
    )
    (comp (ref "S3")
      (value "10-XX")
      (footprint "eagle-import:B3F-10XX")
      (fields (field (name "MPN") "B3F-1000"))
      (libsource (lib "eagle-import") (part "10-XX"))
    )
    (comp (ref "S4")
      (value "10-XX")
      (footprint "eagle-import:B3F-10XX")
      (fields (field (name "MPN") "B3F-1000"))
      (libsource (lib "eagle-import") (part "10-XX"))
    )
    (comp (ref "S5")
      (value "10-XX")
      (footprint "eagle-import:B3F-10XX")
      (fields (field (name "MPN") "B3F-1000"))
      (libsource (lib "eagle-import") (part "10-XX"))
    )
    (comp (ref "S6")
      (value "10-XX")
      (footprint "eagle-import:B3F-10XX")
      (fields (field (name "MPN") "B3F-1000"))
      (libsource (lib "eagle-import") (part "10-XX"))
    )
    (comp (ref "S7")
      (value "10-XX")
      (footprint "eagle-import:B3F-10XX")
      (fields (field (name "MPN") "B3F-1000"))
      (libsource (lib "eagle-import") (part "10-XX"))
    )
    (comp (ref "S8")
      (value "10-XX")
      (footprint "eagle-import:B3F-10XX")
      (fields (field (name "MPN") "B3F-1000"))
      (libsource (lib "eagle-import") (part "10-XX"))
    )
    (comp (ref "C4")
      (value "1uF")
      (footprint "eagle-import:E2,5-5")
      (libsource (lib "eagle-import") (part "CPOL-EUE2.5-5"))
    )
    (comp (ref "C5")
      (value "1uF")
      (footprint "eagle-import:E2,5-5")
      (libsource (lib "eagle-import") (part "CPOL-EUE2.5-5"))
    )
    (comp (ref "C6")
      (value "1uF")
      (footprint "eagle-import:E2,5-5")
      (libsource (lib "eagle-import") (part "CPOL-EUE2.5-5"))
    )
    (comp (ref "C7")
      (value "1uF")
      (footprint "eagle-import:E2,5-5")
      (libsource (lib "eagle-import") (part "CPOL-EUE2.5-5"))
    )
    (comp (ref "IC2")
      (value "MAX232")
      (footprint "eagle-import:DIL16")
      (fields (field (name "MF") "MAXIM") (field (name "MPN") "MAX232ACPE+"))
      (libsource (lib "eagle-import") (part "MAX232"))
    )
  )
  (nets
    (net (code "1") (name "+5V") (class "Default")
      (node (ref "C10") (pin "1") (pinfunction "1_1") (pintype "passive"))
      (node (ref "C11") (pin "1") (pinfunction "1_1") (pintype "passive"))
      (node (ref "C12") (pin "1") (pinfunction "1_1") (pintype "passive"))
      (node (ref "C13") (pin "1") (pinfunction "1_1") (pintype "passive"))
      (node (ref "C8") (pin "1") (pinfunction "1_1") (pintype "passive"))
      (node (ref "IC1") (pin "20") (pinfunction "AVCC_20") (pintype "power_in"))
      (node (ref "IC1") (pin "21") (pinfunction "AREF_21") (pintype "passive"))
      (node (ref "IC1") (pin "7") (pinfunction "VCC_7") (pintype "power_in"))
      (node (ref "IC2") (pin "16") (pinfunction "VCC_16") (pintype "power_in"))
      (node (ref "IC3") (pin "16") (pinfunction "VDD_16") (pintype "power_in"))
      (node (ref "IC4") (pin "1") (pinfunction "A0_1") (pintype "input"))
      (node (ref "IC4") (pin "16") (pinfunction "VDD_16") (pintype "power_in"))
      (node (ref "IC5") (pin "16") (pinfunction "VDD_16") (pintype "power_in"))
      (node (ref "IC5") (pin "2") (pinfunction "A1_2") (pintype "input"))
      (node (ref "IC6") (pin "1") (pinfunction "A0_1") (pintype "input"))
      (node (ref "IC6") (pin "16") (pinfunction "VDD_16") (pintype "power_in"))
      (node (ref "IC6") (pin "2") (pinfunction "A1_2") (pintype "input"))
      (node (ref "JP1") (pin "2") (pinfunction "2_2") (pintype "passive"))
      (node (ref "R1") (pin "2") (pinfunction "2_2") (pintype "passive"))
      (node (ref "R10") (pin "2") (pinfunction "2_2") (pintype "passive"))
      (node (ref "R11") (pin "2") (pinfunction "2_2") (pintype "passive"))
      (node (ref "R12") (pin "2") (pinfunction "2_2") (pintype "passive"))
      (node (ref "R13") (pin "2") (pinfunction "2_2") (pintype "passive"))
      (node (ref "R14") (pin "2") (pinfunction "2_2") (pintype "passive"))
      (node (ref "R15") (pin "2") (pinfunction "2_2") (pintype "passive"))
      (node (ref "R16") (pin "2") (pinfunction "2_2") (pintype "passive"))
      (node (ref "R17") (pin "2") (pinfunction "2_2") (pintype "passive"))
      (node (ref "R18") (pin "2") (pinfunction "2_2") (pintype "passive"))
      (node (ref "R19") (pin "2") (pinfunction "2_2") (pintype "passive"))
      (node (ref "R20") (pin "2") (pinfunction "2_2") (pintype "passive"))
      (node (ref "R21") (pin "2") (pinfunction "2_2") (pintype "passive"))
      (node (ref "R22") (pin "2") (pinfunction "2_2") (pintype "passive"))
      (node (ref "R23") (pin "2") (pinfunction "2_2") (pintype "passive"))
      (node (ref "R24") (pin "2") (pinfunction "2_2") (pintype "passive"))
      (node (ref "R25") (pin "2") (pinfunction "2_2") (pintype "passive"))
      (node (ref "R26") (pin "2") (pinfunction "2_2") (pintype "passive"))
      (node (ref "R27") (pin "2") (pinfunction "2_2") (pintype "passive"))
      (node (ref "R28") (pin "2") (pinfunction "2_2") (pintype "passive"))
      (node (ref "R29") (pin "2") (pinfunction "2_2") (pintype "passive"))
      (node (ref "R3") (pin "1") (pinfunction "1_1") (pintype "passive"))
      (node (ref "R30") (pin "2") (pinfunction "2_2") (pintype "passive"))
      (node (ref "R31") (pin "2") (pinfunction "2_2") (pintype "passive"))
      (node (ref "R32") (pin "2") (pinfunction "2_2") (pintype "passive"))
      (node (ref "R33") (pin "2") (pinfunction "2_2") (pintype "passive"))
      (node (ref "R34") (pin "2") (pinfunction "2_2") (pintype "passive"))
      (node (ref "R35") (pin "2") (pinfunction "2_2") (pintype "passive"))
      (node (ref "R4") (pin "2") (pinfunction "2_2") (pintype "passive"))
      (node (ref "R40") (pin "2") (pinfunction "2_2") (pintype "passive"))
      (node (ref "R41") (pin "2") (pinfunction "2_2") (pintype "passive"))
      (node (ref "R42") (pin "2") (pinfunction "2_2") (pintype "passive"))
      (node (ref "R43") (pin "2") (pinfunction "2_2") (pintype "passive"))
      (node (ref "R44") (pin "2") (pinfunction "2_2") (pintype "passive"))
      (node (ref "R45") (pin "2") (pinfunction "2_2") (pintype "passive"))
      (node (ref "R46") (pin "2") (pinfunction "2_2") (pintype "passive"))
      (node (ref "R5") (pin "2") (pinfunction "2_2") (pintype "passive"))
      (node (ref "R6") (pin "1") (pinfunction "1_1") (pintype "passive"))
      (node (ref "R7") (pin "1") (pinfunction "1_1") (pintype "passive"))
      (node (ref "R8") (pin "1") (pinfunction "1_1") (pintype "passive"))
      (node (ref "R9") (pin "1") (pinfunction "1_1") (pintype "passive"))
      (node (ref "SV1") (pin "2") (pinfunction "2_2") (pintype "passive"))
      (node (ref "U$1") (pin "2") (pinfunction "VDD_2") (pintype "power_in"))
    )
    (net (code "2") (name "BTN0") (class "Default")
      (node (ref "IC3") (pin "4") (pinfunction "P0_4") (pintype "bidirectional"))
      (node (ref "S8") (pin "4") (pinfunction "P1_4") (pintype "passive"))
    )
    (net (code "3") (name "BTN1") (class "Default")
      (node (ref "IC3") (pin "5") (pinfunction "P1_5") (pintype "bidirectional"))
      (node (ref "S7") (pin "3") (pinfunction "P_3") (pintype "passive"))
    )
    (net (code "4") (name "BTN2") (class "Default")
      (node (ref "IC3") (pin "6") (pinfunction "P2_6") (pintype "bidirectional"))
      (node (ref "S6") (pin "4") (pinfunction "P1_4") (pintype "passive"))
    )
    (net (code "5") (name "BTN3") (class "Default")
      (node (ref "IC3") (pin "7") (pinfunction "P3_7") (pintype "bidirectional"))
      (node (ref "S5") (pin "3") (pinfunction "P_3") (pintype "passive"))
    )
    (net (code "6") (name "BTN4") (class "Default")
      (node (ref "IC3") (pin "9") (pinfunction "P4_9") (pintype "bidirectional"))
      (node (ref "S4") (pin "3") (pinfunction "P_3") (pintype "passive"))
    )
    (net (code "7") (name "BTN5") (class "Default")
      (node (ref "IC3") (pin "10") (pinfunction "P5_10") (pintype "bidirectional"))
      (node (ref "S3") (pin "4") (pinfunction "P1_4") (pintype "passive"))
    )
    (net (code "8") (name "BTN6") (class "Default")
      (node (ref "IC3") (pin "11") (pinfunction "P6_11") (pintype "bidirectional"))
      (node (ref "S2") (pin "3") (pinfunction "P_3") (pintype "passive"))
    )
    (net (code "9") (name "BTN7") (class "Default")
      (node (ref "IC3") (pin "12") (pinfunction "P7_12") (pintype "bidirectional"))
      (node (ref "S1") (pin "4") (pinfunction "P1_4") (pintype "passive"))
    )
    (net (code "10") (name "D4") (class "Default")
      (node (ref "IC1") (pin "6") (pinfunction "PD4(XCK/T0)_6") (pintype "bidirectional"))
      (node (ref "U$1") (pin "11") (pinfunction "D4_11") (pintype "bidirectional"))
    )
    (net (code "11") (name "D5") (class "Default")
      (node (ref "IC1") (pin "11") (pinfunction "PD5(T1)_11") (pintype "bidirectional"))
      (node (ref "U$1") (pin "12") (pinfunction "D5_12") (pintype "bidirectional"))
    )
    (net (code "12") (name "D6") (class "Default")
      (node (ref "IC1") (pin "12") (pinfunction "PD6(AIN0)_12") (pintype "bidirectional"))
      (node (ref "U$1") (pin "13") (pinfunction "D6_13") (pintype "bidirectional"))
    )
    (net (code "13") (name "D7") (class "Default")
      (node (ref "IC1") (pin "13") (pinfunction "PD7(AIN1)_13") (pintype "bidirectional"))
      (node (ref "U$1") (pin "14") (pinfunction "D7_14") (pintype "bidirectional"))
    )
    (net (code "14") (name "EN") (class "Default")
      (node (ref "IC1") (pin "16") (pinfunction "PB2(SS/OC1B)_16") (pintype "bidirectional"))
      (node (ref "U$1") (pin "6") (pinfunction "E_6") (pintype "input"))
    )
    (net (code "15") (name "GND") (class "Default")
      (node (ref "C1") (pin "2") (pinfunction "2_2") (pintype "passive"))
      (node (ref "C10") (pin "2") (pinfunction "2_2") (pintype "passive"))
      (node (ref "C11") (pin "2") (pinfunction "2_2") (pintype "passive"))
      (node (ref "C12") (pin "2") (pinfunction "2_2") (pintype "passive"))
      (node (ref "C13") (pin "2") (pinfunction "2_2") (pintype "passive"))
      (node (ref "C2") (pin "2") (pinfunction "2_2") (pintype "passive"))
      (node (ref "C3") (pin "2") (pinfunction "2_2") (pintype "passive"))
      (node (ref "C6") (pin "-") (pinfunction "-_-") (pintype "passive"))
      (node (ref "C7") (pin "+") (pinfunction "+_+") (pintype "passive"))
      (node (ref "C8") (pin "2") (pinfunction "2_2") (pintype "passive"))
      (node (ref "IC1") (pin "22") (pinfunction "GND_22") (pintype "power_in"))
      (node (ref "IC1") (pin "8") (pinfunction "GND_8") (pintype "power_in"))
      (node (ref "IC2") (pin "15") (pinfunction "GND_15") (pintype "power_in"))
      (node (ref "IC3") (pin "1") (pinfunction "A0_1") (pintype "input"))
      (node (ref "IC3") (pin "2") (pinfunction "A1_2") (pintype "input"))
      (node (ref "IC3") (pin "3") (pinfunction "A2_3") (pintype "input"))
      (node (ref "IC3") (pin "8") (pinfunction "VSS_8") (pintype "power_in"))
      (node (ref "IC4") (pin "2") (pinfunction "A1_2") (pintype "input"))
      (node (ref "IC4") (pin "3") (pinfunction "A2_3") (pintype "input"))
      (node (ref "IC4") (pin "8") (pinfunction "VSS_8") (pintype "power_in"))
      (node (ref "IC5") (pin "1") (pinfunction "A0_1") (pintype "input"))
      (node (ref "IC5") (pin "3") (pinfunction "A2_3") (pintype "input"))
      (node (ref "IC5") (pin "8") (pinfunction "VSS_8") (pintype "power_in"))
      (node (ref "IC6") (pin "3") (pinfunction "A2_3") (pintype "input"))
      (node (ref "IC6") (pin "8") (pinfunction "VSS_8") (pintype "power_in"))
      (node (ref "R2") (pin "A") (pinfunction "A_A") (pintype "passive"))
      (node (ref "R36") (pin "1") (pinfunction "1_1") (pintype "passive"))
      (node (ref "R37") (pin "1") (pinfunction "1_1") (pintype "passive"))
      (node (ref "R38") (pin "1") (pinfunction "1_1") (pintype "passive"))
      (node (ref "R39") (pin "1") (pinfunction "1_1") (pintype "passive"))
      (node (ref "S1") (pin "1") (pinfunction "S_1") (pintype "passive"))
      (node (ref "S1") (pin "2") (pinfunction "S1_2") (pintype "passive"))
      (node (ref "S2") (pin "1") (pinfunction "S_1") (pintype "passive"))
      (node (ref "S2") (pin "2") (pinfunction "S1_2") (pintype "passive"))
      (node (ref "S3") (pin "1") (pinfunction "S_1") (pintype "passive"))
      (node (ref "S3") (pin "2") (pinfunction "S1_2") (pintype "passive"))
      (node (ref "S4") (pin "1") (pinfunction "S_1") (pintype "passive"))
      (node (ref "S4") (pin "2") (pinfunction "S1_2") (pintype "passive"))
      (node (ref "S5") (pin "1") (pinfunction "S_1") (pintype "passive"))
      (node (ref "S5") (pin "2") (pinfunction "S1_2") (pintype "passive"))
      (node (ref "S6") (pin "1") (pinfunction "S_1") (pintype "passive"))
      (node (ref "S6") (pin "2") (pinfunction "S1_2") (pintype "passive"))
      (node (ref "S7") (pin "1") (pinfunction "S_1") (pintype "passive"))
      (node (ref "S7") (pin "2") (pinfunction "S1_2") (pintype "passive"))
      (node (ref "S8") (pin "1") (pinfunction "S_1") (pintype "passive"))
      (node (ref "S8") (pin "2") (pinfunction "S1_2") (pintype "passive"))
      (node (ref "SV1") (pin "10") (pinfunction "10_10") (pintype "passive"))
      (node (ref "SV1") (pin "4") (pinfunction "4_4") (pintype "passive"))
      (node (ref "SV1") (pin "6") (pinfunction "6_6") (pintype "passive"))
      (node (ref "SV1") (pin "8") (pinfunction "8_8") (pintype "passive"))
      (node (ref "T1") (pin "2") (pinfunction "E_2") (pintype "passive"))
      (node (ref "T10") (pin "2") (pinfunction "E_2") (pintype "passive"))
      (node (ref "T11") (pin "2") (pinfunction "E_2") (pintype "passive"))
      (node (ref "T12") (pin "2") (pinfunction "E_2") (pintype "passive"))
      (node (ref "T13") (pin "2") (pinfunction "E_2") (pintype "passive"))
      (node (ref "T14") (pin "2") (pinfunction "E_2") (pintype "passive"))
      (node (ref "T15") (pin "2") (pinfunction "E_2") (pintype "passive"))
      (node (ref "T16") (pin "2") (pinfunction "E_2") (pintype "passive"))
      (node (ref "T17") (pin "2") (pinfunction "E_2") (pintype "passive"))
      (node (ref "T18") (pin "2") (pinfunction "E_2") (pintype "passive"))
      (node (ref "T19") (pin "2") (pinfunction "E_2") (pintype "passive"))
      (node (ref "T2") (pin "2") (pinfunction "E_2") (pintype "passive"))
      (node (ref "T20") (pin "2") (pinfunction "E_2") (pintype "passive"))
      (node (ref "T21") (pin "2") (pinfunction "E_2") (pintype "passive"))
      (node (ref "T22") (pin "2") (pinfunction "E_2") (pintype "passive"))
      (node (ref "T23") (pin "2") (pinfunction "E_2") (pintype "passive"))
      (node (ref "T24") (pin "2") (pinfunction "E_2") (pintype "passive"))
      (node (ref "T3") (pin "2") (pinfunction "E_2") (pintype "passive"))
      (node (ref "T4") (pin "2") (pinfunction "E_2") (pintype "passive"))
      (node (ref "T5") (pin "2") (pinfunction "E_2") (pintype "passive"))
      (node (ref "T6") (pin "2") (pinfunction "E_2") (pintype "passive"))
      (node (ref "T7") (pin "2") (pinfunction "E_2") (pintype "passive"))
      (node (ref "T8") (pin "2") (pinfunction "E_2") (pintype "passive"))
      (node (ref "T9") (pin "2") (pinfunction "E_2") (pintype "passive"))
      (node (ref "U$1") (pin "1") (pinfunction "VSS_1") (pintype "power_in"))
      (node (ref "U$1") (pin "16") (pinfunction "LED-_16") (pintype "power_in"))
      (node (ref "X1") (pin "1") (pinfunction "1_1") (pintype "passive"))
      (node (ref "X1") (pin "5") (pinfunction "5_5") (pintype "passive"))
    )
    (net (code "16") (name "LED0") (class "Default")
      (node (ref "IC4") (pin "4") (pinfunction "P0_4") (pintype "bidirectional"))
      (node (ref "T1") (pin "1") (pinfunction "B_1") (pintype "passive"))
    )
    (net (code "17") (name "LED1") (class "Default")
      (node (ref "IC4") (pin "5") (pinfunction "P1_5") (pintype "bidirectional"))
      (node (ref "T2") (pin "1") (pinfunction "B_1") (pintype "passive"))
    )
    (net (code "18") (name "LED2") (class "Default")
      (node (ref "IC4") (pin "6") (pinfunction "P2_6") (pintype "bidirectional"))
      (node (ref "T3") (pin "1") (pinfunction "B_1") (pintype "passive"))
    )
    (net (code "19") (name "LED3") (class "Default")
      (node (ref "IC4") (pin "7") (pinfunction "P3_7") (pintype "bidirectional"))
      (node (ref "T4") (pin "1") (pinfunction "B_1") (pintype "passive"))
    )
    (net (code "20") (name "LED4") (class "Default")
      (node (ref "IC4") (pin "9") (pinfunction "P4_9") (pintype "bidirectional"))
      (node (ref "T5") (pin "1") (pinfunction "B_1") (pintype "passive"))
    )
    (net (code "21") (name "LED5") (class "Default")
      (node (ref "IC4") (pin "10") (pinfunction "P5_10") (pintype "bidirectional"))
      (node (ref "T6") (pin "1") (pinfunction "B_1") (pintype "passive"))
    )
    (net (code "22") (name "LED6") (class "Default")
      (node (ref "IC4") (pin "11") (pinfunction "P6_11") (pintype "bidirectional"))
      (node (ref "T7") (pin "1") (pinfunction "B_1") (pintype "passive"))
    )
    (net (code "23") (name "LED7") (class "Default")
      (node (ref "IC4") (pin "12") (pinfunction "P7_12") (pintype "bidirectional"))
      (node (ref "T8") (pin "1") (pinfunction "B_1") (pintype "passive"))
    )
    (net (code "24") (name "LED8") (class "Default")
      (node (ref "IC5") (pin "4") (pinfunction "P0_4") (pintype "bidirectional"))
      (node (ref "T9") (pin "1") (pinfunction "B_1") (pintype "passive"))
    )
    (net (code "25") (name "LED9") (class "Default")
      (node (ref "IC5") (pin "5") (pinfunction "P1_5") (pintype "bidirectional"))
      (node (ref "T10") (pin "1") (pinfunction "B_1") (pintype "passive"))
    )
    (net (code "26") (name "LED10") (class "Default")
      (node (ref "IC5") (pin "6") (pinfunction "P2_6") (pintype "bidirectional"))
      (node (ref "T11") (pin "1") (pinfunction "B_1") (pintype "passive"))
    )
    (net (code "27") (name "LED11") (class "Default")
      (node (ref "IC5") (pin "7") (pinfunction "P3_7") (pintype "bidirectional"))
      (node (ref "T12") (pin "1") (pinfunction "B_1") (pintype "passive"))
    )
    (net (code "28") (name "LED12") (class "Default")
      (node (ref "IC5") (pin "9") (pinfunction "P4_9") (pintype "bidirectional"))
      (node (ref "T13") (pin "1") (pinfunction "B_1") (pintype "passive"))
    )
    (net (code "29") (name "LED13") (class "Default")
      (node (ref "IC5") (pin "10") (pinfunction "P5_10") (pintype "bidirectional"))
      (node (ref "T14") (pin "1") (pinfunction "B_1") (pintype "passive"))
    )
    (net (code "30") (name "LED14") (class "Default")
      (node (ref "IC5") (pin "11") (pinfunction "P6_11") (pintype "bidirectional"))
      (node (ref "T15") (pin "1") (pinfunction "B_1") (pintype "passive"))
    )
    (net (code "31") (name "LED15") (class "Default")
      (node (ref "IC5") (pin "12") (pinfunction "P7_12") (pintype "bidirectional"))
      (node (ref "T16") (pin "1") (pinfunction "B_1") (pintype "passive"))
    )
    (net (code "32") (name "LED16") (class "Default")
      (node (ref "IC6") (pin "4") (pinfunction "P0_4") (pintype "bidirectional"))
      (node (ref "T17") (pin "1") (pinfunction "B_1") (pintype "passive"))
    )
    (net (code "33") (name "LED17") (class "Default")
      (node (ref "IC6") (pin "5") (pinfunction "P1_5") (pintype "bidirectional"))
      (node (ref "T18") (pin "1") (pinfunction "B_1") (pintype "passive"))
    )
    (net (code "34") (name "LED18") (class "Default")
      (node (ref "IC6") (pin "6") (pinfunction "P2_6") (pintype "bidirectional"))
      (node (ref "T19") (pin "1") (pinfunction "B_1") (pintype "passive"))
    )
    (net (code "35") (name "LED19") (class "Default")
      (node (ref "IC6") (pin "7") (pinfunction "P3_7") (pintype "bidirectional"))
      (node (ref "T20") (pin "1") (pinfunction "B_1") (pintype "passive"))
    )
    (net (code "36") (name "LED20") (class "Default")
      (node (ref "IC6") (pin "9") (pinfunction "P4_9") (pintype "bidirectional"))
      (node (ref "T21") (pin "1") (pinfunction "B_1") (pintype "passive"))
    )
    (net (code "37") (name "LED21") (class "Default")
      (node (ref "IC6") (pin "10") (pinfunction "P5_10") (pintype "bidirectional"))
      (node (ref "T22") (pin "1") (pinfunction "B_1") (pintype "passive"))
    )
    (net (code "38") (name "LED22") (class "Default")
      (node (ref "IC6") (pin "11") (pinfunction "P6_11") (pintype "bidirectional"))
      (node (ref "T23") (pin "1") (pinfunction "B_1") (pintype "passive"))
    )
    (net (code "39") (name "LED23") (class "Default")
      (node (ref "IC6") (pin "12") (pinfunction "P7_12") (pintype "bidirectional"))
      (node (ref "T24") (pin "1") (pinfunction "B_1") (pintype "passive"))
    )
    (net (code "40") (name "MISO") (class "Default")
      (node (ref "IC1") (pin "18") (pinfunction "PB4(MISO)_18") (pintype "bidirectional"))
      (node (ref "SV1") (pin "9") (pinfunction "9_9") (pintype "passive"))
    )
    (net (code "41") (name "MOSI") (class "Default")
      (node (ref "IC1") (pin "17") (pinfunction "PB3(MOSI/OC2)_17") (pintype "bidirectional"))
      (node (ref "SV1") (pin "1") (pinfunction "1_1") (pintype "passive"))
    )
    (net (code "42") (name "Net-(IC1-PB6(XTAL1{slash}TOSC1))") (class "Default")
      (node (ref "C2") (pin "1") (pinfunction "1_1") (pintype "passive"))
      (node (ref "IC1") (pin "9") (pinfunction "PB6(XTAL1/TOSC1)_9") (pintype "bidirectional"))
      (node (ref "Q1") (pin "1") (pinfunction "1_1") (pintype "passive"))
    )
    (net (code "43") (name "Net-(IC1-PB7(XTAL2{slash}TOSC2))") (class "Default")
      (node (ref "C3") (pin "1") (pinfunction "1_1") (pintype "passive"))
      (node (ref "IC1") (pin "10") (pinfunction "PB7(XTAL2/TOSC2)_10") (pintype "bidirectional"))
      (node (ref "Q1") (pin "2") (pinfunction "2_2") (pintype "passive"))
    )
    (net (code "44") (name "Net-(IC1-PC0(ADC0))") (class "Default")
      (node (ref "IC1") (pin "23") (pinfunction "PC0(ADC0)_23") (pintype "bidirectional"))
      (node (ref "LED28") (pin "A") (pinfunction "A_A") (pintype "passive"))
    )
    (net (code "45") (name "Net-(IC1-PC1(ADC1))") (class "Default")
      (node (ref "IC1") (pin "24") (pinfunction "PC1(ADC1)_24") (pintype "bidirectional"))
      (node (ref "LED27") (pin "A") (pinfunction "A_A") (pintype "passive"))
    )
    (net (code "46") (name "Net-(IC1-PC2(ADC2))") (class "Default")
      (node (ref "IC1") (pin "25") (pinfunction "PC2(ADC2)_25") (pintype "bidirectional"))
      (node (ref "LED26") (pin "A") (pinfunction "A_A") (pintype "passive"))
    )
    (net (code "47") (name "Net-(IC1-PC3(ADC3))") (class "Default")
      (node (ref "IC1") (pin "26") (pinfunction "PC3(ADC3)_26") (pintype "bidirectional"))
      (node (ref "LED25") (pin "A") (pinfunction "A_A") (pintype "passive"))
    )
    (net (code "48") (name "Net-(IC2A-C1+)") (class "Default")
      (node (ref "C4") (pin "+") (pinfunction "+_+") (pintype "passive"))
      (node (ref "IC2") (pin "1") (pinfunction "C1+_1") (pintype "bidirectional"))
    )
    (net (code "49") (name "Net-(IC2A-C1-)") (class "Default")
      (node (ref "C4") (pin "-") (pinfunction "-_-") (pintype "passive"))
      (node (ref "IC2") (pin "3") (pinfunction "C1-_3") (pintype "bidirectional"))
    )
    (net (code "50") (name "Net-(IC2A-C2+)") (class "Default")
      (node (ref "C5") (pin "+") (pinfunction "+_+") (pintype "passive"))
      (node (ref "IC2") (pin "4") (pinfunction "C2+_4") (pintype "bidirectional"))
    )
    (net (code "51") (name "Net-(IC2A-C2-)") (class "Default")
      (node (ref "C5") (pin "-") (pinfunction "-_-") (pintype "passive"))
      (node (ref "IC2") (pin "5") (pinfunction "C2-_5") (pintype "bidirectional"))
    )
    (net (code "52") (name "Net-(IC2A-V+)") (class "Default")
      (node (ref "C6") (pin "+") (pinfunction "+_+") (pintype "passive"))
      (node (ref "IC2") (pin "2") (pinfunction "V+_2") (pintype "bidirectional"))
    )
    (net (code "53") (name "Net-(IC2A-V-)") (class "Default")
      (node (ref "C7") (pin "-") (pinfunction "-_-") (pintype "passive"))
      (node (ref "IC2") (pin "6") (pinfunction "V-_6") (pintype "bidirectional"))
    )
    (net (code "54") (name "Net-(IC3-~{INT})") (class "Default")
      (node (ref "IC3") (pin "13") (pinfunction "~{INT}_13") (pintype "output"))
      (node (ref "R6") (pin "2") (pinfunction "2_2") (pintype "passive"))
    )
    (net (code "55") (name "Net-(IC4-~{INT})") (class "Default")
      (node (ref "IC4") (pin "13") (pinfunction "~{INT}_13") (pintype "output"))
      (node (ref "R7") (pin "2") (pinfunction "2_2") (pintype "passive"))
    )
    (net (code "56") (name "Net-(IC5-~{INT})") (class "Default")
      (node (ref "IC5") (pin "13") (pinfunction "~{INT}_13") (pintype "output"))
      (node (ref "R8") (pin "2") (pinfunction "2_2") (pintype "passive"))
    )
    (net (code "57") (name "Net-(IC6-~{INT})") (class "Default")
      (node (ref "IC6") (pin "13") (pinfunction "~{INT}_13") (pintype "output"))
      (node (ref "R9") (pin "2") (pinfunction "2_2") (pintype "passive"))
    )
    (net (code "58") (name "Net-(JP1-Pad1)") (class "Default")
      (node (ref "JP1") (pin "1") (pinfunction "1_1") (pintype "passive"))
      (node (ref "X1") (pin "9") (pinfunction "9_9") (pintype "passive"))
    )
    (net (code "59") (name "Net-(LED1-C)") (class "Default")
      (node (ref "LED1") (pin "K") (pinfunction "C_K") (pintype "passive"))
      (node (ref "T1") (pin "3") (pinfunction "C_3") (pintype "passive"))
    )
    (net (code "60") (name "Net-(LED1-PadA)") (class "Default")
      (node (ref "LED1") (pin "A") (pinfunction "A_A") (pintype "passive"))
      (node (ref "R12") (pin "1") (pinfunction "1_1") (pintype "passive"))
    )
    (net (code "61") (name "Net-(LED2-C)") (class "Default")
      (node (ref "LED2") (pin "K") (pinfunction "C_K") (pintype "passive"))
      (node (ref "T2") (pin "3") (pinfunction "C_3") (pintype "passive"))
    )
    (net (code "62") (name "Net-(LED2-PadA)") (class "Default")
      (node (ref "LED2") (pin "A") (pinfunction "A_A") (pintype "passive"))
      (node (ref "R13") (pin "1") (pinfunction "1_1") (pintype "passive"))
    )
    (net (code "63") (name "Net-(LED3-C)") (class "Default")
      (node (ref "LED3") (pin "K") (pinfunction "C_K") (pintype "passive"))
      (node (ref "T3") (pin "3") (pinfunction "C_3") (pintype "passive"))
    )
    (net (code "64") (name "Net-(LED3-PadA)") (class "Default")
      (node (ref "LED3") (pin "A") (pinfunction "A_A") (pintype "passive"))
      (node (ref "R14") (pin "1") (pinfunction "1_1") (pintype "passive"))
    )
    (net (code "65") (name "Net-(LED4-C)") (class "Default")
      (node (ref "LED4") (pin "K") (pinfunction "C_K") (pintype "passive"))
      (node (ref "T4") (pin "3") (pinfunction "C_3") (pintype "passive"))
    )
    (net (code "66") (name "Net-(LED4-PadA)") (class "Default")
      (node (ref "LED4") (pin "A") (pinfunction "A_A") (pintype "passive"))
      (node (ref "R15") (pin "1") (pinfunction "1_1") (pintype "passive"))
    )
    (net (code "67") (name "Net-(LED5-C)") (class "Default")
      (node (ref "LED5") (pin "K") (pinfunction "C_K") (pintype "passive"))
      (node (ref "T5") (pin "3") (pinfunction "C_3") (pintype "passive"))
    )
    (net (code "68") (name "Net-(LED5-PadA)") (class "Default")
      (node (ref "LED5") (pin "A") (pinfunction "A_A") (pintype "passive"))
      (node (ref "R16") (pin "1") (pinfunction "1_1") (pintype "passive"))
    )
    (net (code "69") (name "Net-(LED6-C)") (class "Default")
      (node (ref "LED6") (pin "K") (pinfunction "C_K") (pintype "passive"))
      (node (ref "T6") (pin "3") (pinfunction "C_3") (pintype "passive"))
    )
    (net (code "70") (name "Net-(LED6-PadA)") (class "Default")
      (node (ref "LED6") (pin "A") (pinfunction "A_A") (pintype "passive"))
      (node (ref "R17") (pin "1") (pinfunction "1_1") (pintype "passive"))
    )
    (net (code "71") (name "Net-(LED7-C)") (class "Default")
      (node (ref "LED7") (pin "K") (pinfunction "C_K") (pintype "passive"))
      (node (ref "T7") (pin "3") (pinfunction "C_3") (pintype "passive"))
    )
    (net (code "72") (name "Net-(LED7-PadA)") (class "Default")
      (node (ref "LED7") (pin "A") (pinfunction "A_A") (pintype "passive"))
      (node (ref "R18") (pin "1") (pinfunction "1_1") (pintype "passive"))
    )
    (net (code "73") (name "Net-(LED8-C)") (class "Default")
      (node (ref "LED8") (pin "K") (pinfunction "C_K") (pintype "passive"))
      (node (ref "T8") (pin "3") (pinfunction "C_3") (pintype "passive"))
    )
    (net (code "74") (name "Net-(LED8-PadA)") (class "Default")
      (node (ref "LED8") (pin "A") (pinfunction "A_A") (pintype "passive"))
      (node (ref "R19") (pin "1") (pinfunction "1_1") (pintype "passive"))
    )
    (net (code "75") (name "Net-(LED9-C)") (class "Default")
      (node (ref "LED9") (pin "K") (pinfunction "C_K") (pintype "passive"))
      (node (ref "T9") (pin "3") (pinfunction "C_3") (pintype "passive"))
    )
    (net (code "76") (name "Net-(LED9-PadA)") (class "Default")
      (node (ref "LED9") (pin "A") (pinfunction "A_A") (pintype "passive"))
      (node (ref "R20") (pin "1") (pinfunction "1_1") (pintype "passive"))
    )
    (net (code "77") (name "Net-(LED10-C)") (class "Default")
      (node (ref "LED10") (pin "K") (pinfunction "C_K") (pintype "passive"))
      (node (ref "T10") (pin "3") (pinfunction "C_3") (pintype "passive"))
    )
    (net (code "78") (name "Net-(LED10-PadA)") (class "Default")
      (node (ref "LED10") (pin "A") (pinfunction "A_A") (pintype "passive"))
      (node (ref "R21") (pin "1") (pinfunction "1_1") (pintype "passive"))
    )
    (net (code "79") (name "Net-(LED11-C)") (class "Default")
      (node (ref "LED11") (pin "K") (pinfunction "C_K") (pintype "passive"))
      (node (ref "T11") (pin "3") (pinfunction "C_3") (pintype "passive"))
    )
    (net (code "80") (name "Net-(LED11-PadA)") (class "Default")
      (node (ref "LED11") (pin "A") (pinfunction "A_A") (pintype "passive"))
      (node (ref "R22") (pin "1") (pinfunction "1_1") (pintype "passive"))
    )
    (net (code "81") (name "Net-(LED12-C)") (class "Default")
      (node (ref "LED12") (pin "K") (pinfunction "C_K") (pintype "passive"))
      (node (ref "T12") (pin "3") (pinfunction "C_3") (pintype "passive"))
    )
    (net (code "82") (name "Net-(LED12-PadA)") (class "Default")
      (node (ref "LED12") (pin "A") (pinfunction "A_A") (pintype "passive"))
      (node (ref "R23") (pin "1") (pinfunction "1_1") (pintype "passive"))
    )
    (net (code "83") (name "Net-(LED13-C)") (class "Default")
      (node (ref "LED13") (pin "K") (pinfunction "C_K") (pintype "passive"))
      (node (ref "T13") (pin "3") (pinfunction "C_3") (pintype "passive"))
    )
    (net (code "84") (name "Net-(LED13-PadA)") (class "Default")
      (node (ref "LED13") (pin "A") (pinfunction "A_A") (pintype "passive"))
      (node (ref "R24") (pin "1") (pinfunction "1_1") (pintype "passive"))
    )
    (net (code "85") (name "Net-(LED14-C)") (class "Default")
      (node (ref "LED14") (pin "K") (pinfunction "C_K") (pintype "passive"))
      (node (ref "T14") (pin "3") (pinfunction "C_3") (pintype "passive"))
    )
    (net (code "86") (name "Net-(LED14-PadA)") (class "Default")
      (node (ref "LED14") (pin "A") (pinfunction "A_A") (pintype "passive"))
      (node (ref "R25") (pin "1") (pinfunction "1_1") (pintype "passive"))
    )
    (net (code "87") (name "Net-(LED15-C)") (class "Default")
      (node (ref "LED15") (pin "K") (pinfunction "C_K") (pintype "passive"))
      (node (ref "T15") (pin "3") (pinfunction "C_3") (pintype "passive"))
    )
    (net (code "88") (name "Net-(LED15-PadA)") (class "Default")
      (node (ref "LED15") (pin "A") (pinfunction "A_A") (pintype "passive"))
      (node (ref "R26") (pin "1") (pinfunction "1_1") (pintype "passive"))
    )
    (net (code "89") (name "Net-(LED16-C)") (class "Default")
      (node (ref "LED16") (pin "K") (pinfunction "C_K") (pintype "passive"))
      (node (ref "T16") (pin "3") (pinfunction "C_3") (pintype "passive"))
    )
    (net (code "90") (name "Net-(LED16-PadA)") (class "Default")
      (node (ref "LED16") (pin "A") (pinfunction "A_A") (pintype "passive"))
      (node (ref "R27") (pin "1") (pinfunction "1_1") (pintype "passive"))
    )
    (net (code "91") (name "Net-(LED17-C)") (class "Default")
      (node (ref "LED17") (pin "K") (pinfunction "C_K") (pintype "passive"))
      (node (ref "T17") (pin "3") (pinfunction "C_3") (pintype "passive"))
    )
    (net (code "92") (name "Net-(LED17-PadA)") (class "Default")
      (node (ref "LED17") (pin "A") (pinfunction "A_A") (pintype "passive"))
      (node (ref "R28") (pin "1") (pinfunction "1_1") (pintype "passive"))
    )
    (net (code "93") (name "Net-(LED18-C)") (class "Default")
      (node (ref "LED18") (pin "K") (pinfunction "C_K") (pintype "passive"))
      (node (ref "T18") (pin "3") (pinfunction "C_3") (pintype "passive"))
    )
    (net (code "94") (name "Net-(LED18-PadA)") (class "Default")
      (node (ref "LED18") (pin "A") (pinfunction "A_A") (pintype "passive"))
      (node (ref "R29") (pin "1") (pinfunction "1_1") (pintype "passive"))
    )
    (net (code "95") (name "Net-(LED19-C)") (class "Default")
      (node (ref "LED19") (pin "K") (pinfunction "C_K") (pintype "passive"))
      (node (ref "T19") (pin "3") (pinfunction "C_3") (pintype "passive"))
    )
    (net (code "96") (name "Net-(LED19-PadA)") (class "Default")
      (node (ref "LED19") (pin "A") (pinfunction "A_A") (pintype "passive"))
      (node (ref "R30") (pin "1") (pinfunction "1_1") (pintype "passive"))
    )
    (net (code "97") (name "Net-(LED20-C)") (class "Default")
      (node (ref "LED20") (pin "K") (pinfunction "C_K") (pintype "passive"))
      (node (ref "T20") (pin "3") (pinfunction "C_3") (pintype "passive"))
    )
    (net (code "98") (name "Net-(LED20-PadA)") (class "Default")
      (node (ref "LED20") (pin "A") (pinfunction "A_A") (pintype "passive"))
      (node (ref "R31") (pin "1") (pinfunction "1_1") (pintype "passive"))
    )
    (net (code "99") (name "Net-(LED21-C)") (class "Default")
      (node (ref "LED21") (pin "K") (pinfunction "C_K") (pintype "passive"))
      (node (ref "T21") (pin "3") (pinfunction "C_3") (pintype "passive"))
    )
    (net (code "100") (name "Net-(LED21-PadA)") (class "Default")
      (node (ref "LED21") (pin "A") (pinfunction "A_A") (pintype "passive"))
      (node (ref "R32") (pin "1") (pinfunction "1_1") (pintype "passive"))
    )
    (net (code "101") (name "Net-(LED22-C)") (class "Default")
      (node (ref "LED22") (pin "K") (pinfunction "C_K") (pintype "passive"))
      (node (ref "T22") (pin "3") (pinfunction "C_3") (pintype "passive"))
    )
    (net (code "102") (name "Net-(LED22-PadA)") (class "Default")
      (node (ref "LED22") (pin "A") (pinfunction "A_A") (pintype "passive"))
      (node (ref "R33") (pin "1") (pinfunction "1_1") (pintype "passive"))
    )
    (net (code "103") (name "Net-(LED23-C)") (class "Default")
      (node (ref "LED23") (pin "K") (pinfunction "C_K") (pintype "passive"))
      (node (ref "T23") (pin "3") (pinfunction "C_3") (pintype "passive"))
    )
    (net (code "104") (name "Net-(LED23-PadA)") (class "Default")
      (node (ref "LED23") (pin "A") (pinfunction "A_A") (pintype "passive"))
      (node (ref "R34") (pin "1") (pinfunction "1_1") (pintype "passive"))
    )
    (net (code "105") (name "Net-(LED24-C)") (class "Default")
      (node (ref "LED24") (pin "K") (pinfunction "C_K") (pintype "passive"))
      (node (ref "T24") (pin "3") (pinfunction "C_3") (pintype "passive"))
    )
    (net (code "106") (name "Net-(LED24-PadA)") (class "Default")
      (node (ref "LED24") (pin "A") (pinfunction "A_A") (pintype "passive"))
      (node (ref "R35") (pin "1") (pinfunction "1_1") (pintype "passive"))
    )
    (net (code "107") (name "Net-(LED25-C)") (class "Default")
      (node (ref "LED25") (pin "K") (pinfunction "C_K") (pintype "passive"))
      (node (ref "R36") (pin "2") (pinfunction "2_2") (pintype "passive"))
    )
    (net (code "108") (name "Net-(LED26-C)") (class "Default")
      (node (ref "LED26") (pin "K") (pinfunction "C_K") (pintype "passive"))
      (node (ref "R37") (pin "2") (pinfunction "2_2") (pintype "passive"))
    )
    (net (code "109") (name "Net-(LED27-C)") (class "Default")
      (node (ref "LED27") (pin "K") (pinfunction "C_K") (pintype "passive"))
      (node (ref "R38") (pin "2") (pinfunction "2_2") (pintype "passive"))
    )
    (net (code "110") (name "Net-(LED28-C)") (class "Default")
      (node (ref "LED28") (pin "K") (pinfunction "C_K") (pintype "passive"))
      (node (ref "R39") (pin "2") (pinfunction "2_2") (pintype "passive"))
    )
    (net (code "111") (name "Net-(R2-PadE)") (class "Default")
      (node (ref "R2") (pin "E") (pinfunction "E_E") (pintype "passive"))
      (node (ref "R3") (pin "2") (pinfunction "2_2") (pintype "passive"))
    )
    (net (code "112") (name "Net-(S1-P)") (class "Default")
      (node (ref "R46") (pin "1") (pinfunction "1_1") (pintype "passive"))
      (node (ref "S1") (pin "3") (pinfunction "P_3") (pintype "passive"))
    )
    (net (code "113") (name "Net-(S2-P1)") (class "Default")
      (node (ref "R45") (pin "1") (pinfunction "1_1") (pintype "passive"))
      (node (ref "S2") (pin "4") (pinfunction "P1_4") (pintype "passive"))
    )
    (net (code "114") (name "Net-(S3-P)") (class "Default")
      (node (ref "R44") (pin "1") (pinfunction "1_1") (pintype "passive"))
      (node (ref "S3") (pin "3") (pinfunction "P_3") (pintype "passive"))
    )
    (net (code "115") (name "Net-(S4-P1)") (class "Default")
      (node (ref "R43") (pin "1") (pinfunction "1_1") (pintype "passive"))
      (node (ref "S4") (pin "4") (pinfunction "P1_4") (pintype "passive"))
    )
    (net (code "116") (name "Net-(S5-P1)") (class "Default")
      (node (ref "R42") (pin "1") (pinfunction "1_1") (pintype "passive"))
      (node (ref "S5") (pin "4") (pinfunction "P1_4") (pintype "passive"))
    )
    (net (code "117") (name "Net-(S6-P)") (class "Default")
      (node (ref "R41") (pin "1") (pinfunction "1_1") (pintype "passive"))
      (node (ref "S6") (pin "3") (pinfunction "P_3") (pintype "passive"))
    )
    (net (code "118") (name "Net-(S7-P1)") (class "Default")
      (node (ref "R40") (pin "1") (pinfunction "1_1") (pintype "passive"))
      (node (ref "S7") (pin "4") (pinfunction "P1_4") (pintype "passive"))
    )
    (net (code "119") (name "Net-(S8-P)") (class "Default")
      (node (ref "R4") (pin "1") (pinfunction "1_1") (pintype "passive"))
      (node (ref "S8") (pin "3") (pinfunction "P_3") (pintype "passive"))
    )
    (net (code "120") (name "Net-(U$1-LED+)") (class "Default")
      (node (ref "R5") (pin "1") (pinfunction "1_1") (pintype "passive"))
      (node (ref "U$1") (pin "15") (pinfunction "LED+_15") (pintype "power_in"))
    )
    (net (code "121") (name "Net-(U$1-VEE)") (class "Default")
      (node (ref "R2") (pin "S") (pinfunction "S_S") (pintype "passive"))
      (node (ref "U$1") (pin "3") (pinfunction "VEE_3") (pintype "input"))
    )
    (net (code "122") (name "RESET") (class "Default")
      (node (ref "C1") (pin "1") (pinfunction "1_1") (pintype "passive"))
      (node (ref "IC1") (pin "1") (pinfunction "PC6(/RESET)_1") (pintype "bidirectional"))
      (node (ref "R1") (pin "1") (pinfunction "1_1") (pintype "passive"))
      (node (ref "SV1") (pin "5") (pinfunction "5_5") (pintype "passive"))
    )
    (net (code "123") (name "RS") (class "Default")
      (node (ref "IC1") (pin "14") (pinfunction "PB0(ICP)_14") (pintype "bidirectional"))
      (node (ref "U$1") (pin "4") (pinfunction "RS_4") (pintype "input"))
    )
    (net (code "124") (name "RS232RX") (class "Default")
      (node (ref "IC2") (pin "14") (pinfunction "T1OUT_14") (pintype "output"))
      (node (ref "JP2") (pin "1") (pinfunction "1_1") (pintype "passive"))
      (node (ref "JP2") (pin "6") (pinfunction "6_6") (pintype "passive"))
    )
    (net (code "125") (name "RS232RX_CON") (class "Default")
      (node (ref "JP2") (pin "3") (pinfunction "3_3") (pintype "passive"))
      (node (ref "X1") (pin "2") (pinfunction "2_2") (pintype "passive"))
    )
    (net (code "126") (name "RS232TX") (class "Default")
      (node (ref "IC2") (pin "13") (pinfunction "R1IN_13") (pintype "input"))
      (node (ref "JP2") (pin "2") (pinfunction "2_2") (pintype "passive"))
      (node (ref "JP2") (pin "5") (pinfunction "5_5") (pintype "passive"))
    )
    (net (code "127") (name "RS232TX_CON") (class "Default")
      (node (ref "JP2") (pin "4") (pinfunction "4_4") (pintype "passive"))
      (node (ref "X1") (pin "3") (pinfunction "3_3") (pintype "passive"))
    )
    (net (code "128") (name "RW") (class "Default")
      (node (ref "IC1") (pin "15") (pinfunction "PB1(OC1A)_15") (pintype "bidirectional"))
      (node (ref "U$1") (pin "5") (pinfunction "R/W_5") (pintype "input"))
    )
    (net (code "129") (name "RXD") (class "Default")
      (node (ref "IC1") (pin "2") (pinfunction "PD0(RXD)_2") (pintype "bidirectional"))
      (node (ref "IC2") (pin "12") (pinfunction "R1OUT_12") (pintype "output"))
    )
    (net (code "130") (name "SCK") (class "Default")
      (node (ref "IC1") (pin "19") (pinfunction "PB5(SCK)_19") (pintype "bidirectional"))
      (node (ref "SV1") (pin "7") (pinfunction "7_7") (pintype "passive"))
    )
    (net (code "131") (name "SCL") (class "Default")
      (node (ref "IC1") (pin "28") (pinfunction "PC5(ADC5/SCL)_28") (pintype "bidirectional"))
      (node (ref "IC3") (pin "14") (pinfunction "SCL_14") (pintype "input"))
      (node (ref "IC4") (pin "14") (pinfunction "SCL_14") (pintype "input"))
      (node (ref "IC5") (pin "14") (pinfunction "SCL_14") (pintype "input"))
      (node (ref "IC6") (pin "14") (pinfunction "SCL_14") (pintype "input"))
      (node (ref "R11") (pin "1") (pinfunction "1_1") (pintype "passive"))
    )
    (net (code "132") (name "SDA") (class "Default")
      (node (ref "IC1") (pin "27") (pinfunction "PC4(ADC4/SDA)_27") (pintype "bidirectional"))
      (node (ref "IC3") (pin "15") (pinfunction "SDA_15") (pintype "bidirectional"))
      (node (ref "IC4") (pin "15") (pinfunction "SDA_15") (pintype "bidirectional"))
      (node (ref "IC5") (pin "15") (pinfunction "SDA_15") (pintype "bidirectional"))
      (node (ref "IC6") (pin "15") (pinfunction "SDA_15") (pintype "bidirectional"))
      (node (ref "R10") (pin "1") (pinfunction "1_1") (pintype "passive"))
    )
    (net (code "133") (name "TXD") (class "Default")
      (node (ref "IC1") (pin "3") (pinfunction "PD1(TXD)_3") (pintype "bidirectional"))
      (node (ref "IC2") (pin "11") (pinfunction "T1IN_11") (pintype "input"))
    )
    (net (code "134") (name "unconnected-(IC1-PD2(INT0)-Pad4)") (class "Default")
      (node (ref "IC1") (pin "4") (pinfunction "PD2(INT0)_4") (pintype "bidirectional"))
    )
    (net (code "135") (name "unconnected-(IC1-PD3(INT1)-Pad5)") (class "Default")
      (node (ref "IC1") (pin "5") (pinfunction "PD3(INT1)_5") (pintype "bidirectional"))
    )
    (net (code "136") (name "unconnected-(IC2A-R2IN-Pad8)") (class "Default")
      (node (ref "IC2") (pin "8") (pinfunction "R2IN_8") (pintype "input"))
    )
    (net (code "137") (name "unconnected-(IC2A-R2OUT-Pad9)") (class "Default")
      (node (ref "IC2") (pin "9") (pinfunction "R2OUT_9") (pintype "output"))
    )
    (net (code "138") (name "unconnected-(IC2A-T2IN-Pad10)") (class "Default")
      (node (ref "IC2") (pin "10") (pinfunction "T2IN_10") (pintype "input"))
    )
    (net (code "139") (name "unconnected-(IC2A-T2OUT-Pad7)") (class "Default")
      (node (ref "IC2") (pin "7") (pinfunction "T2OUT_7") (pintype "output"))
    )
    (net (code "140") (name "unconnected-(SV1-Pad3)") (class "Default")
      (node (ref "SV1") (pin "3") (pinfunction "3_3") (pintype "passive"))
    )
    (net (code "141") (name "unconnected-(U$1-D0-Pad7)") (class "Default")
      (node (ref "U$1") (pin "7") (pinfunction "D0_7") (pintype "bidirectional"))
    )
    (net (code "142") (name "unconnected-(U$1-D1-Pad8)") (class "Default")
      (node (ref "U$1") (pin "8") (pinfunction "D1_8") (pintype "bidirectional"))
    )
    (net (code "143") (name "unconnected-(U$1-D2-Pad9)") (class "Default")
      (node (ref "U$1") (pin "9") (pinfunction "D2_9") (pintype "bidirectional"))
    )
    (net (code "144") (name "unconnected-(U$1-D3-Pad10)") (class "Default")
      (node (ref "U$1") (pin "10") (pinfunction "D3_10") (pintype "bidirectional"))
    )
    (net (code "145") (name "unconnected-(X1-Pad4)") (class "Default")
      (node (ref "X1") (pin "4") (pinfunction "4_4") (pintype "passive"))
    )
    (net (code "146") (name "unconnected-(X1-Pad6)") (class "Default")
      (node (ref "X1") (pin "6") (pinfunction "6_6") (pintype "passive"))
    )
    (net (code "147") (name "unconnected-(X1-Pad7)") (class "Default")
      (node (ref "X1") (pin "7") (pinfunction "7_7") (pintype "passive"))
    )
    (net (code "148") (name "unconnected-(X1-Pad8)") (class "Default")
      (node (ref "X1") (pin "8") (pinfunction "8_8") (pintype "passive"))
    )
  )
)
